# sch.net
KiCad netlist of a schematic drawn in EasyEDA
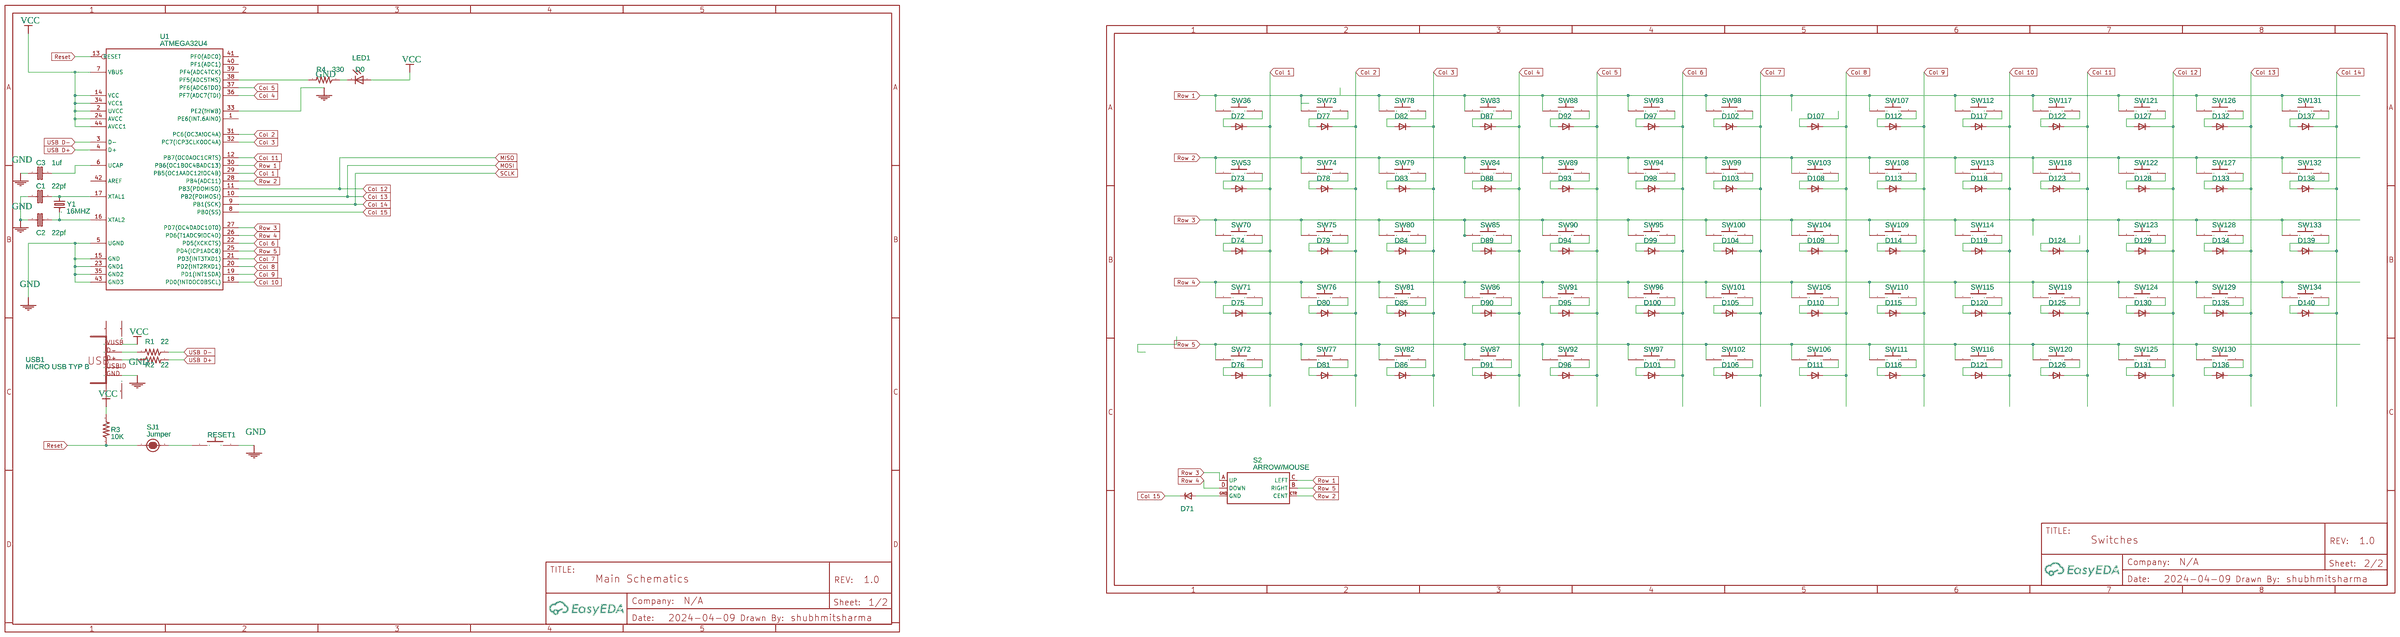
[diagram p0: Sheet_1]
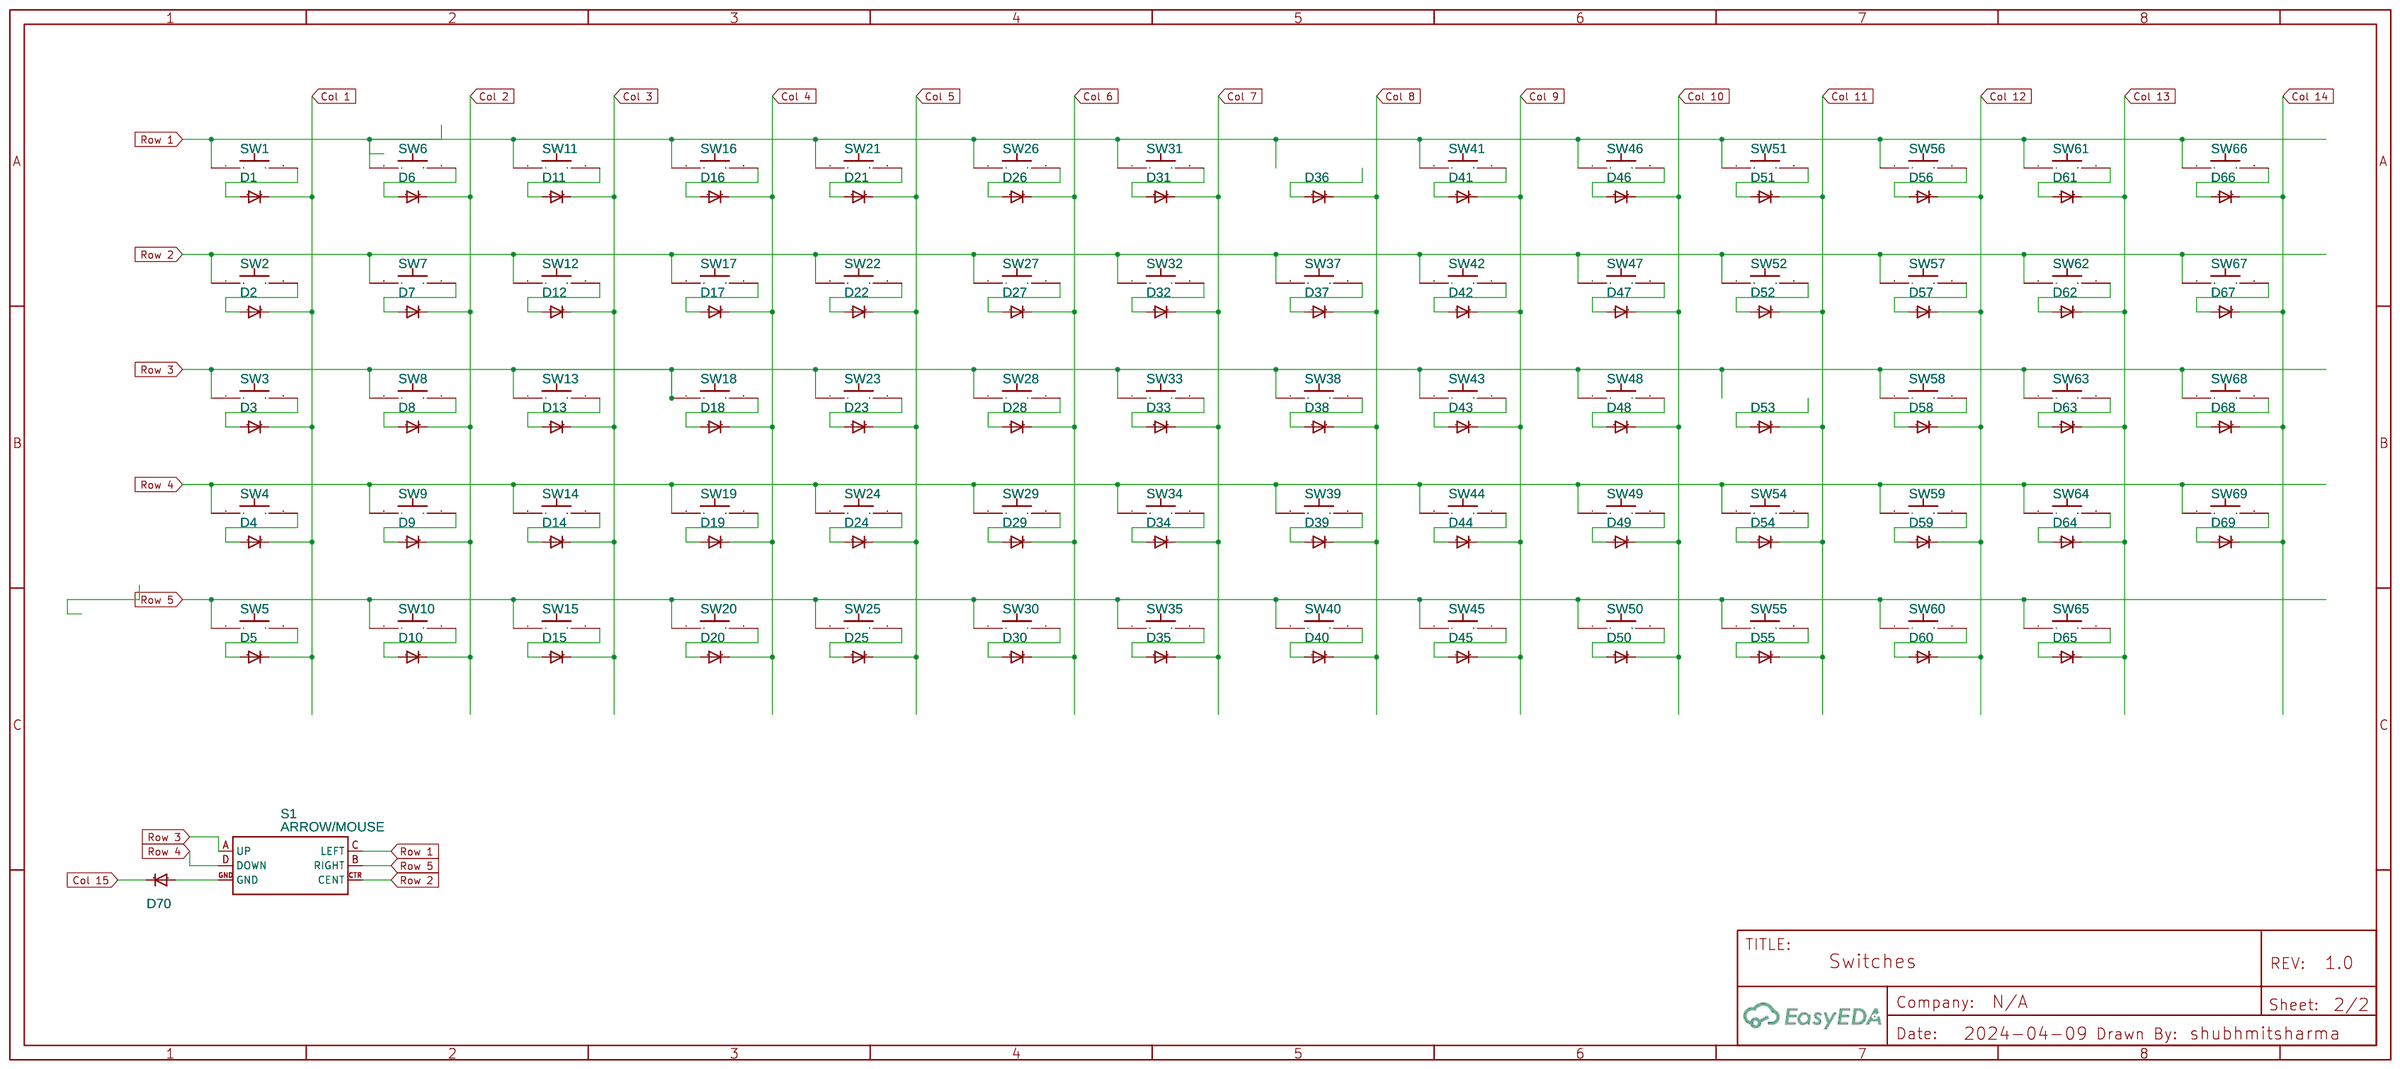
[diagram p1: Sheet_1#2]

(export (version "E")
  (design (tool "Eeschema 10.0.6"))
  (components
    (comp (ref "C1")
      (value "22pf")
      (fields (field (name "Manufacturer Part") "?"))
      (libsource (lib "") (part "Unknown_50_-560"))
    )
    (comp (ref "C2")
      (value "22pf")
      (fields (field (name "Manufacturer Part") "?"))
      (libsource (lib "") (part "Unknown_40_-530"))
    )
    (comp (ref "C3")
      (value "1uf")
      (fields (field (name "Manufacturer Part") "?"))
      (libsource (lib "") (part "Unknown_50_-590"))
    )
    (comp (ref "D71")
      (value "NO")
      (fields (field (name "Manufacturer Part") "?"))
      (libsource (lib "") (part "Unknown_1520_-175"))
    )
    (comp (ref "D72")
      (value "NO")
      (fields (field (name "Manufacturer Part") "?"))
      (libsource (lib "") (part "Unknown_1585_-650"))
    )
    (comp (ref "D73")
      (value "NO")
      (fields (field (name "Manufacturer Part") "?"))
      (libsource (lib "") (part "Unknown_1585_-570"))
    )
    (comp (ref "D74")
      (value "NO")
      (fields (field (name "Manufacturer Part") "?"))
      (libsource (lib "") (part "Unknown_1585_-490"))
    )
    (comp (ref "D75")
      (value "NO")
      (fields (field (name "Manufacturer Part") "?"))
      (libsource (lib "") (part "Unknown_1585_-410"))
    )
    (comp (ref "D76")
      (value "NO")
      (fields (field (name "Manufacturer Part") "?"))
      (libsource (lib "") (part "Unknown_1585_-330"))
    )
    (comp (ref "D77")
      (value "NO")
      (fields (field (name "Manufacturer Part") "?"))
      (libsource (lib "") (part "Unknown_1695_-650"))
    )
    (comp (ref "D78")
      (value "NO")
      (fields (field (name "Manufacturer Part") "?"))
      (libsource (lib "") (part "Unknown_1695_-570"))
    )
    (comp (ref "D79")
      (value "NO")
      (fields (field (name "Manufacturer Part") "?"))
      (libsource (lib "") (part "Unknown_1695_-490"))
    )
    (comp (ref "D80")
      (value "NO")
      (fields (field (name "Manufacturer Part") "?"))
      (libsource (lib "") (part "Unknown_1695_-410"))
    )
    (comp (ref "D81")
      (value "NO")
      (fields (field (name "Manufacturer Part") "?"))
      (libsource (lib "") (part "Unknown_1695_-330"))
    )
    (comp (ref "D82")
      (value "NO")
      (fields (field (name "Manufacturer Part") "?"))
      (libsource (lib "") (part "Unknown_1795_-650"))
    )
    (comp (ref "D83")
      (value "NO")
      (fields (field (name "Manufacturer Part") "?"))
      (libsource (lib "") (part "Unknown_1795_-570"))
    )
    (comp (ref "D84")
      (value "NO")
      (fields (field (name "Manufacturer Part") "?"))
      (libsource (lib "") (part "Unknown_1795_-490"))
    )
    (comp (ref "D85")
      (value "NO")
      (fields (field (name "Manufacturer Part") "?"))
      (libsource (lib "") (part "Unknown_1795_-410"))
    )
    (comp (ref "D86")
      (value "NO")
      (fields (field (name "Manufacturer Part") "?"))
      (libsource (lib "") (part "Unknown_1795_-330"))
    )
    (comp (ref "D87")
      (value "NO")
      (fields (field (name "Manufacturer Part") "?"))
      (libsource (lib "") (part "Unknown_1905_-650"))
    )
    (comp (ref "D88")
      (value "NO")
      (fields (field (name "Manufacturer Part") "?"))
      (libsource (lib "") (part "Unknown_1905_-570"))
    )
    (comp (ref "D89")
      (value "NO")
      (fields (field (name "Manufacturer Part") "?"))
      (libsource (lib "") (part "Unknown_1905_-490"))
    )
    (comp (ref "D90")
      (value "NO")
      (fields (field (name "Manufacturer Part") "?"))
      (libsource (lib "") (part "Unknown_1905_-410"))
    )
    (comp (ref "D91")
      (value "NO")
      (fields (field (name "Manufacturer Part") "?"))
      (libsource (lib "") (part "Unknown_1905_-330"))
    )
    (comp (ref "D92")
      (value "NO")
      (fields (field (name "Manufacturer Part") "?"))
      (libsource (lib "") (part "Unknown_2005_-650"))
    )
    (comp (ref "D93")
      (value "NO")
      (fields (field (name "Manufacturer Part") "?"))
      (libsource (lib "") (part "Unknown_2005_-570"))
    )
    (comp (ref "D94")
      (value "NO")
      (fields (field (name "Manufacturer Part") "?"))
      (libsource (lib "") (part "Unknown_2005_-490"))
    )
    (comp (ref "D95")
      (value "NO")
      (fields (field (name "Manufacturer Part") "?"))
      (libsource (lib "") (part "Unknown_2005_-410"))
    )
    (comp (ref "D96")
      (value "NO")
      (fields (field (name "Manufacturer Part") "?"))
      (libsource (lib "") (part "Unknown_2005_-330"))
    )
    (comp (ref "D97")
      (value "NO")
      (fields (field (name "Manufacturer Part") "?"))
      (libsource (lib "") (part "Unknown_2115_-650"))
    )
    (comp (ref "D98")
      (value "NO")
      (fields (field (name "Manufacturer Part") "?"))
      (libsource (lib "") (part "Unknown_2115_-570"))
    )
    (comp (ref "D99")
      (value "NO")
      (fields (field (name "Manufacturer Part") "?"))
      (libsource (lib "") (part "Unknown_2115_-490"))
    )
    (comp (ref "D100")
      (value "NO")
      (fields (field (name "Manufacturer Part") "?"))
      (libsource (lib "") (part "Unknown_2115_-410"))
    )
    (comp (ref "D101")
      (value "NO")
      (fields (field (name "Manufacturer Part") "?"))
      (libsource (lib "") (part "Unknown_2115_-330"))
    )
    (comp (ref "D102")
      (value "NO")
      (fields (field (name "Manufacturer Part") "?"))
      (libsource (lib "") (part "Unknown_2215_-650"))
    )
    (comp (ref "D103")
      (value "NO")
      (fields (field (name "Manufacturer Part") "?"))
      (libsource (lib "") (part "Unknown_2215_-570"))
    )
    (comp (ref "D104")
      (value "NO")
      (fields (field (name "Manufacturer Part") "?"))
      (libsource (lib "") (part "Unknown_2215_-490"))
    )
    (comp (ref "D105")
      (value "NO")
      (fields (field (name "Manufacturer Part") "?"))
      (libsource (lib "") (part "Unknown_2215_-410"))
    )
    (comp (ref "D106")
      (value "NO")
      (fields (field (name "Manufacturer Part") "?"))
      (libsource (lib "") (part "Unknown_2215_-330"))
    )
    (comp (ref "D107")
      (value "NO")
      (fields (field (name "Manufacturer Part") "?"))
      (libsource (lib "") (part "Unknown_2325_-650"))
    )
    (comp (ref "D108")
      (value "NO")
      (fields (field (name "Manufacturer Part") "?"))
      (libsource (lib "") (part "Unknown_2325_-570"))
    )
    (comp (ref "D109")
      (value "NO")
      (fields (field (name "Manufacturer Part") "?"))
      (libsource (lib "") (part "Unknown_2325_-490"))
    )
    (comp (ref "D110")
      (value "NO")
      (fields (field (name "Manufacturer Part") "?"))
      (libsource (lib "") (part "Unknown_2325_-410"))
    )
    (comp (ref "D111")
      (value "NO")
      (fields (field (name "Manufacturer Part") "?"))
      (libsource (lib "") (part "Unknown_2325_-330"))
    )
    (comp (ref "D112")
      (value "NO")
      (fields (field (name "Manufacturer Part") "?"))
      (libsource (lib "") (part "Unknown_2425_-650"))
    )
    (comp (ref "D113")
      (value "NO")
      (fields (field (name "Manufacturer Part") "?"))
      (libsource (lib "") (part "Unknown_2425_-570"))
    )
    (comp (ref "D114")
      (value "NO")
      (fields (field (name "Manufacturer Part") "?"))
      (libsource (lib "") (part "Unknown_2425_-490"))
    )
    (comp (ref "D115")
      (value "NO")
      (fields (field (name "Manufacturer Part") "?"))
      (libsource (lib "") (part "Unknown_2425_-410"))
    )
    (comp (ref "D116")
      (value "NO")
      (fields (field (name "Manufacturer Part") "?"))
      (libsource (lib "") (part "Unknown_2425_-330"))
    )
    (comp (ref "D117")
      (value "NO")
      (fields (field (name "Manufacturer Part") "?"))
      (libsource (lib "") (part "Unknown_2535_-650"))
    )
    (comp (ref "D118")
      (value "NO")
      (fields (field (name "Manufacturer Part") "?"))
      (libsource (lib "") (part "Unknown_2535_-570"))
    )
    (comp (ref "D119")
      (value "NO")
      (fields (field (name "Manufacturer Part") "?"))
      (libsource (lib "") (part "Unknown_2535_-490"))
    )
    (comp (ref "D120")
      (value "NO")
      (fields (field (name "Manufacturer Part") "?"))
      (libsource (lib "") (part "Unknown_2535_-410"))
    )
    (comp (ref "D121")
      (value "NO")
      (fields (field (name "Manufacturer Part") "?"))
      (libsource (lib "") (part "Unknown_2535_-330"))
    )
    (comp (ref "D122")
      (value "NO")
      (fields (field (name "Manufacturer Part") "?"))
      (libsource (lib "") (part "Unknown_2635_-650"))
    )
    (comp (ref "D123")
      (value "NO")
      (fields (field (name "Manufacturer Part") "?"))
      (libsource (lib "") (part "Unknown_2635_-570"))
    )
    (comp (ref "D124")
      (value "NO")
      (fields (field (name "Manufacturer Part") "?"))
      (libsource (lib "") (part "Unknown_2635_-490"))
    )
    (comp (ref "D125")
      (value "NO")
      (fields (field (name "Manufacturer Part") "?"))
      (libsource (lib "") (part "Unknown_2635_-410"))
    )
    (comp (ref "D126")
      (value "NO")
      (fields (field (name "Manufacturer Part") "?"))
      (libsource (lib "") (part "Unknown_2635_-330"))
    )
    (comp (ref "D127")
      (value "NO")
      (fields (field (name "Manufacturer Part") "?"))
      (libsource (lib "") (part "Unknown_2745_-650"))
    )
    (comp (ref "D128")
      (value "NO")
      (fields (field (name "Manufacturer Part") "?"))
      (libsource (lib "") (part "Unknown_2745_-570"))
    )
    (comp (ref "D129")
      (value "NO")
      (fields (field (name "Manufacturer Part") "?"))
      (libsource (lib "") (part "Unknown_2745_-490"))
    )
    (comp (ref "D130")
      (value "NO")
      (fields (field (name "Manufacturer Part") "?"))
      (libsource (lib "") (part "Unknown_2745_-410"))
    )
    (comp (ref "D131")
      (value "NO")
      (fields (field (name "Manufacturer Part") "?"))
      (libsource (lib "") (part "Unknown_2745_-330"))
    )
    (comp (ref "D132")
      (value "NO")
      (fields (field (name "Manufacturer Part") "?"))
      (libsource (lib "") (part "Unknown_2845_-650"))
    )
    (comp (ref "D133")
      (value "NO")
      (fields (field (name "Manufacturer Part") "?"))
      (libsource (lib "") (part "Unknown_2845_-570"))
    )
    (comp (ref "D134")
      (value "NO")
      (fields (field (name "Manufacturer Part") "?"))
      (libsource (lib "") (part "Unknown_2845_-490"))
    )
    (comp (ref "D135")
      (value "NO")
      (fields (field (name "Manufacturer Part") "?"))
      (libsource (lib "") (part "Unknown_2845_-410"))
    )
    (comp (ref "D136")
      (value "NO")
      (fields (field (name "Manufacturer Part") "?"))
      (libsource (lib "") (part "Unknown_2845_-330"))
    )
    (comp (ref "D137")
      (value "NO")
      (fields (field (name "Manufacturer Part") "?"))
      (libsource (lib "") (part "Unknown_2955_-650"))
    )
    (comp (ref "D138")
      (value "NO")
      (fields (field (name "Manufacturer Part") "?"))
      (libsource (lib "") (part "Unknown_2955_-570"))
    )
    (comp (ref "D139")
      (value "NO")
      (fields (field (name "Manufacturer Part") "?"))
      (libsource (lib "") (part "Unknown_2955_-490"))
    )
    (comp (ref "D140")
      (value "NO")
      (fields (field (name "Manufacturer Part") "?"))
      (libsource (lib "") (part "Unknown_2955_-410"))
    )
    (comp (ref "LED1")
      (value "D0")
      (fields (field (name "Manufacturer Part") "?"))
      (libsource (lib "") (part "Unknown_460_-710"))
    )
    (comp (ref "R1")
      (value "22")
      (fields (field (name "Manufacturer Part") "?"))
      (libsource (lib "") (part "Unknown_190_-360"))
    )
    (comp (ref "R2")
      (value "22")
      (fields (field (name "Manufacturer Part") "?"))
      (libsource (lib "") (part "Unknown_190_-350"))
    )
    (comp (ref "R3")
      (value "10K")
      (fields (field (name "Manufacturer Part") "?"))
      (libsource (lib "") (part "Unknown_130_-260"))
    )
    (comp (ref "R4")
      (value "330")
      (fields (field (name "Manufacturer Part") "?"))
      (libsource (lib "") (part "Unknown_410_-710"))
    )
    (comp (ref "RESET1")
      (value "NO")
      (fields (field (name "Manufacturer Part") "?"))
      (libsource (lib "") (part "Unknown_270_-240"))
    )
    (comp (ref "S2")
      (value "ARROW/MOUSE")
      (fields (field (name "Manufacturer Part") "?"))
      (libsource (lib "") (part "Unknown_1610_-185"))
    )
    (comp (ref "SJ1")
      (value "Jumper")
      (fields (field (name "Manufacturer Part") "?"))
      (libsource (lib "") (part "Unknown_190_-240"))
    )
    (comp (ref "SW36")
      (value "NO")
      (fields (field (name "Manufacturer Part") "?"))
      (libsource (lib "") (part "Unknown_1585_-670"))
    )
    (comp (ref "SW53")
      (value "NO")
      (fields (field (name "Manufacturer Part") "?"))
      (libsource (lib "") (part "Unknown_1585_-590"))
    )
    (comp (ref "SW70")
      (value "NO")
      (fields (field (name "Manufacturer Part") "?"))
      (libsource (lib "") (part "Unknown_1585_-510"))
    )
    (comp (ref "SW71")
      (value "NO")
      (fields (field (name "Manufacturer Part") "?"))
      (libsource (lib "") (part "Unknown_1585_-430"))
    )
    (comp (ref "SW72")
      (value "NO")
      (fields (field (name "Manufacturer Part") "?"))
      (libsource (lib "") (part "Unknown_1585_-350"))
    )
    (comp (ref "SW73")
      (value "NO")
      (fields (field (name "Manufacturer Part") "?"))
      (libsource (lib "") (part "Unknown_1695_-670"))
    )
    (comp (ref "SW74")
      (value "NO")
      (fields (field (name "Manufacturer Part") "?"))
      (libsource (lib "") (part "Unknown_1695_-590"))
    )
    (comp (ref "SW75")
      (value "NO")
      (fields (field (name "Manufacturer Part") "?"))
      (libsource (lib "") (part "Unknown_1695_-510"))
    )
    (comp (ref "SW76")
      (value "NO")
      (fields (field (name "Manufacturer Part") "?"))
      (libsource (lib "") (part "Unknown_1695_-430"))
    )
    (comp (ref "SW77")
      (value "NO")
      (fields (field (name "Manufacturer Part") "?"))
      (libsource (lib "") (part "Unknown_1695_-350"))
    )
    (comp (ref "SW78")
      (value "NO")
      (fields (field (name "Manufacturer Part") "?"))
      (libsource (lib "") (part "Unknown_1795_-670"))
    )
    (comp (ref "SW79")
      (value "NO")
      (fields (field (name "Manufacturer Part") "?"))
      (libsource (lib "") (part "Unknown_1795_-590"))
    )
    (comp (ref "SW80")
      (value "NO")
      (fields (field (name "Manufacturer Part") "?"))
      (libsource (lib "") (part "Unknown_1795_-510"))
    )
    (comp (ref "SW81")
      (value "NO")
      (fields (field (name "Manufacturer Part") "?"))
      (libsource (lib "") (part "Unknown_1795_-430"))
    )
    (comp (ref "SW82")
      (value "NO")
      (fields (field (name "Manufacturer Part") "?"))
      (libsource (lib "") (part "Unknown_1795_-350"))
    )
    (comp (ref "SW83")
      (value "NO")
      (fields (field (name "Manufacturer Part") "?"))
      (libsource (lib "") (part "Unknown_1905_-670"))
    )
    (comp (ref "SW84")
      (value "NO")
      (fields (field (name "Manufacturer Part") "?"))
      (libsource (lib "") (part "Unknown_1905_-590"))
    )
    (comp (ref "SW85")
      (value "NO")
      (fields (field (name "Manufacturer Part") "?"))
      (libsource (lib "") (part "Unknown_1905_-510"))
    )
    (comp (ref "SW86")
      (value "NO")
      (fields (field (name "Manufacturer Part") "?"))
      (libsource (lib "") (part "Unknown_1905_-430"))
    )
    (comp (ref "SW87")
      (value "NO")
      (fields (field (name "Manufacturer Part") "?"))
      (libsource (lib "") (part "Unknown_1905_-350"))
    )
    (comp (ref "SW88")
      (value "NO")
      (fields (field (name "Manufacturer Part") "?"))
      (libsource (lib "") (part "Unknown_2005_-670"))
    )
    (comp (ref "SW89")
      (value "NO")
      (fields (field (name "Manufacturer Part") "?"))
      (libsource (lib "") (part "Unknown_2005_-590"))
    )
    (comp (ref "SW90")
      (value "NO")
      (fields (field (name "Manufacturer Part") "?"))
      (libsource (lib "") (part "Unknown_2005_-510"))
    )
    (comp (ref "SW91")
      (value "NO")
      (fields (field (name "Manufacturer Part") "?"))
      (libsource (lib "") (part "Unknown_2005_-430"))
    )
    (comp (ref "SW92")
      (value "NO")
      (fields (field (name "Manufacturer Part") "?"))
      (libsource (lib "") (part "Unknown_2005_-350"))
    )
    (comp (ref "SW93")
      (value "NO")
      (fields (field (name "Manufacturer Part") "?"))
      (libsource (lib "") (part "Unknown_2115_-670"))
    )
    (comp (ref "SW94")
      (value "NO")
      (fields (field (name "Manufacturer Part") "?"))
      (libsource (lib "") (part "Unknown_2115_-590"))
    )
    (comp (ref "SW95")
      (value "NO")
      (fields (field (name "Manufacturer Part") "?"))
      (libsource (lib "") (part "Unknown_2115_-510"))
    )
    (comp (ref "SW96")
      (value "NO")
      (fields (field (name "Manufacturer Part") "?"))
      (libsource (lib "") (part "Unknown_2115_-430"))
    )
    (comp (ref "SW97")
      (value "NO")
      (fields (field (name "Manufacturer Part") "?"))
      (libsource (lib "") (part "Unknown_2115_-350"))
    )
    (comp (ref "SW98")
      (value "NO")
      (fields (field (name "Manufacturer Part") "?"))
      (libsource (lib "") (part "Unknown_2215_-670"))
    )
    (comp (ref "SW99")
      (value "NO")
      (fields (field (name "Manufacturer Part") "?"))
      (libsource (lib "") (part "Unknown_2215_-590"))
    )
    (comp (ref "SW100")
      (value "NO")
      (fields (field (name "Manufacturer Part") "?"))
      (libsource (lib "") (part "Unknown_2215_-510"))
    )
    (comp (ref "SW101")
      (value "NO")
      (fields (field (name "Manufacturer Part") "?"))
      (libsource (lib "") (part "Unknown_2215_-430"))
    )
    (comp (ref "SW102")
      (value "NO")
      (fields (field (name "Manufacturer Part") "?"))
      (libsource (lib "") (part "Unknown_2215_-350"))
    )
    (comp (ref "SW103")
      (value "NO")
      (fields (field (name "Manufacturer Part") "?"))
      (libsource (lib "") (part "Unknown_2325_-590"))
    )
    (comp (ref "SW104")
      (value "NO")
      (fields (field (name "Manufacturer Part") "?"))
      (libsource (lib "") (part "Unknown_2325_-510"))
    )
    (comp (ref "SW105")
      (value "NO")
      (fields (field (name "Manufacturer Part") "?"))
      (libsource (lib "") (part "Unknown_2325_-430"))
    )
    (comp (ref "SW106")
      (value "NO")
      (fields (field (name "Manufacturer Part") "?"))
      (libsource (lib "") (part "Unknown_2325_-350"))
    )
    (comp (ref "SW107")
      (value "NO")
      (fields (field (name "Manufacturer Part") "?"))
      (libsource (lib "") (part "Unknown_2425_-670"))
    )
    (comp (ref "SW108")
      (value "NO")
      (fields (field (name "Manufacturer Part") "?"))
      (libsource (lib "") (part "Unknown_2425_-590"))
    )
    (comp (ref "SW109")
      (value "NO")
      (fields (field (name "Manufacturer Part") "?"))
      (libsource (lib "") (part "Unknown_2425_-510"))
    )
    (comp (ref "SW110")
      (value "NO")
      (fields (field (name "Manufacturer Part") "?"))
      (libsource (lib "") (part "Unknown_2425_-430"))
    )
    (comp (ref "SW111")
      (value "NO")
      (fields (field (name "Manufacturer Part") "?"))
      (libsource (lib "") (part "Unknown_2425_-350"))
    )
    (comp (ref "SW112")
      (value "NO")
      (fields (field (name "Manufacturer Part") "?"))
      (libsource (lib "") (part "Unknown_2535_-670"))
    )
    (comp (ref "SW113")
      (value "NO")
      (fields (field (name "Manufacturer Part") "?"))
      (libsource (lib "") (part "Unknown_2535_-590"))
    )
    (comp (ref "SW114")
      (value "NO")
      (fields (field (name "Manufacturer Part") "?"))
      (libsource (lib "") (part "Unknown_2535_-510"))
    )
    (comp (ref "SW115")
      (value "NO")
      (fields (field (name "Manufacturer Part") "?"))
      (libsource (lib "") (part "Unknown_2535_-430"))
    )
    (comp (ref "SW116")
      (value "NO")
      (fields (field (name "Manufacturer Part") "?"))
      (libsource (lib "") (part "Unknown_2535_-350"))
    )
    (comp (ref "SW117")
      (value "NO")
      (fields (field (name "Manufacturer Part") "?"))
      (libsource (lib "") (part "Unknown_2635_-670"))
    )
    (comp (ref "SW118")
      (value "NO")
      (fields (field (name "Manufacturer Part") "?"))
      (libsource (lib "") (part "Unknown_2635_-590"))
    )
    (comp (ref "SW119")
      (value "NO")
      (fields (field (name "Manufacturer Part") "?"))
      (libsource (lib "") (part "Unknown_2635_-430"))
    )
    (comp (ref "SW120")
      (value "NO")
      (fields (field (name "Manufacturer Part") "?"))
      (libsource (lib "") (part "Unknown_2635_-350"))
    )
    (comp (ref "SW121")
      (value "NO")
      (fields (field (name "Manufacturer Part") "?"))
      (libsource (lib "") (part "Unknown_2745_-670"))
    )
    (comp (ref "SW122")
      (value "NO")
      (fields (field (name "Manufacturer Part") "?"))
      (libsource (lib "") (part "Unknown_2745_-590"))
    )
    (comp (ref "SW123")
      (value "NO")
      (fields (field (name "Manufacturer Part") "?"))
      (libsource (lib "") (part "Unknown_2745_-510"))
    )
    (comp (ref "SW124")
      (value "NO")
      (fields (field (name "Manufacturer Part") "?"))
      (libsource (lib "") (part "Unknown_2745_-430"))
    )
    (comp (ref "SW125")
      (value "NO")
      (fields (field (name "Manufacturer Part") "?"))
      (libsource (lib "") (part "Unknown_2745_-350"))
    )
    (comp (ref "SW126")
      (value "NO")
      (fields (field (name "Manufacturer Part") "?"))
      (libsource (lib "") (part "Unknown_2845_-670"))
    )
    (comp (ref "SW127")
      (value "NO")
      (fields (field (name "Manufacturer Part") "?"))
      (libsource (lib "") (part "Unknown_2845_-590"))
    )
    (comp (ref "SW128")
      (value "NO")
      (fields (field (name "Manufacturer Part") "?"))
      (libsource (lib "") (part "Unknown_2845_-510"))
    )
    (comp (ref "SW129")
      (value "NO")
      (fields (field (name "Manufacturer Part") "?"))
      (libsource (lib "") (part "Unknown_2845_-430"))
    )
    (comp (ref "SW130")
      (value "NO")
      (fields (field (name "Manufacturer Part") "?"))
      (libsource (lib "") (part "Unknown_2845_-350"))
    )
    (comp (ref "SW131")
      (value "NO")
      (fields (field (name "Manufacturer Part") "?"))
      (libsource (lib "") (part "Unknown_2955_-670"))
    )
    (comp (ref "SW132")
      (value "NO")
      (fields (field (name "Manufacturer Part") "?"))
      (libsource (lib "") (part "Unknown_2955_-590"))
    )
    (comp (ref "SW133")
      (value "NO")
      (fields (field (name "Manufacturer Part") "?"))
      (libsource (lib "") (part "Unknown_2955_-510"))
    )
    (comp (ref "SW134")
      (value "NO")
      (fields (field (name "Manufacturer Part") "?"))
      (libsource (lib "") (part "Unknown_2955_-430"))
    )
    (comp (ref "U1")
      (value "ATMEGA32U4")
      (fields (field (name "Manufacturer Part") "?"))
      (libsource (lib "") (part "Unknown_200_-570"))
    )
    (comp (ref "USB1")
      (value "MICRO USB TYP B")
      (fields (field (name "Manufacturer Part") "?"))
      (libsource (lib "") (part "Unknown_130_-350"))
    )
    (comp (ref "Y1")
      (value "16MHZ")
      (fields (field (name "Manufacturer Part") "?"))
      (libsource (lib "") (part "Unknown_70_-550"))
    )
    (comp (ref "D1")
      (value "NO")
      (fields (field (name "Manufacturer Part") "?"))
      (libsource (lib "") (part "Unknown_380_-535"))
    )
    (comp (ref "D2")
      (value "NO")
      (fields (field (name "Manufacturer Part") "?"))
      (libsource (lib "") (part "Unknown_380_-455"))
    )
    (comp (ref "D3")
      (value "NO")
      (fields (field (name "Manufacturer Part") "?"))
      (libsource (lib "") (part "Unknown_380_-375"))
    )
    (comp (ref "D4")
      (value "NO")
      (fields (field (name "Manufacturer Part") "?"))
      (libsource (lib "") (part "Unknown_380_-295"))
    )
    (comp (ref "D5")
      (value "NO")
      (fields (field (name "Manufacturer Part") "?"))
      (libsource (lib "") (part "Unknown_380_-215"))
    )
    (comp (ref "D6")
      (value "NO")
      (fields (field (name "Manufacturer Part") "?"))
      (libsource (lib "") (part "Unknown_490_-535"))
    )
    (comp (ref "D7")
      (value "NO")
      (fields (field (name "Manufacturer Part") "?"))
      (libsource (lib "") (part "Unknown_490_-455"))
    )
    (comp (ref "D8")
      (value "NO")
      (fields (field (name "Manufacturer Part") "?"))
      (libsource (lib "") (part "Unknown_490_-375"))
    )
    (comp (ref "D9")
      (value "NO")
      (fields (field (name "Manufacturer Part") "?"))
      (libsource (lib "") (part "Unknown_490_-295"))
    )
    (comp (ref "D10")
      (value "NO")
      (fields (field (name "Manufacturer Part") "?"))
      (libsource (lib "") (part "Unknown_490_-215"))
    )
    (comp (ref "D11")
      (value "NO")
      (fields (field (name "Manufacturer Part") "?"))
      (libsource (lib "") (part "Unknown_590_-535"))
    )
    (comp (ref "D12")
      (value "NO")
      (fields (field (name "Manufacturer Part") "?"))
      (libsource (lib "") (part "Unknown_590_-455"))
    )
    (comp (ref "D13")
      (value "NO")
      (fields (field (name "Manufacturer Part") "?"))
      (libsource (lib "") (part "Unknown_590_-375"))
    )
    (comp (ref "D14")
      (value "NO")
      (fields (field (name "Manufacturer Part") "?"))
      (libsource (lib "") (part "Unknown_590_-295"))
    )
    (comp (ref "D15")
      (value "NO")
      (fields (field (name "Manufacturer Part") "?"))
      (libsource (lib "") (part "Unknown_590_-215"))
    )
    (comp (ref "D16")
      (value "NO")
      (fields (field (name "Manufacturer Part") "?"))
      (libsource (lib "") (part "Unknown_700_-535"))
    )
    (comp (ref "D17")
      (value "NO")
      (fields (field (name "Manufacturer Part") "?"))
      (libsource (lib "") (part "Unknown_700_-455"))
    )
    (comp (ref "D18")
      (value "NO")
      (fields (field (name "Manufacturer Part") "?"))
      (libsource (lib "") (part "Unknown_700_-375"))
    )
    (comp (ref "D19")
      (value "NO")
      (fields (field (name "Manufacturer Part") "?"))
      (libsource (lib "") (part "Unknown_700_-295"))
    )
    (comp (ref "D20")
      (value "NO")
      (fields (field (name "Manufacturer Part") "?"))
      (libsource (lib "") (part "Unknown_700_-215"))
    )
    (comp (ref "D21")
      (value "NO")
      (fields (field (name "Manufacturer Part") "?"))
      (libsource (lib "") (part "Unknown_800_-535"))
    )
    (comp (ref "D22")
      (value "NO")
      (fields (field (name "Manufacturer Part") "?"))
      (libsource (lib "") (part "Unknown_800_-455"))
    )
    (comp (ref "D23")
      (value "NO")
      (fields (field (name "Manufacturer Part") "?"))
      (libsource (lib "") (part "Unknown_800_-375"))
    )
    (comp (ref "D24")
      (value "NO")
      (fields (field (name "Manufacturer Part") "?"))
      (libsource (lib "") (part "Unknown_800_-295"))
    )
    (comp (ref "D25")
      (value "NO")
      (fields (field (name "Manufacturer Part") "?"))
      (libsource (lib "") (part "Unknown_800_-215"))
    )
    (comp (ref "D26")
      (value "NO")
      (fields (field (name "Manufacturer Part") "?"))
      (libsource (lib "") (part "Unknown_910_-535"))
    )
    (comp (ref "D27")
      (value "NO")
      (fields (field (name "Manufacturer Part") "?"))
      (libsource (lib "") (part "Unknown_910_-455"))
    )
    (comp (ref "D28")
      (value "NO")
      (fields (field (name "Manufacturer Part") "?"))
      (libsource (lib "") (part "Unknown_910_-375"))
    )
    (comp (ref "D29")
      (value "NO")
      (fields (field (name "Manufacturer Part") "?"))
      (libsource (lib "") (part "Unknown_910_-295"))
    )
    (comp (ref "D30")
      (value "NO")
      (fields (field (name "Manufacturer Part") "?"))
      (libsource (lib "") (part "Unknown_910_-215"))
    )
    (comp (ref "D31")
      (value "NO")
      (fields (field (name "Manufacturer Part") "?"))
      (libsource (lib "") (part "Unknown_1010_-535"))
    )
    (comp (ref "D32")
      (value "NO")
      (fields (field (name "Manufacturer Part") "?"))
      (libsource (lib "") (part "Unknown_1010_-455"))
    )
    (comp (ref "D33")
      (value "NO")
      (fields (field (name "Manufacturer Part") "?"))
      (libsource (lib "") (part "Unknown_1010_-375"))
    )
    (comp (ref "D34")
      (value "NO")
      (fields (field (name "Manufacturer Part") "?"))
      (libsource (lib "") (part "Unknown_1010_-295"))
    )
    (comp (ref "D35")
      (value "NO")
      (fields (field (name "Manufacturer Part") "?"))
      (libsource (lib "") (part "Unknown_1010_-215"))
    )
    (comp (ref "D36")
      (value "NO")
      (fields (field (name "Manufacturer Part") "?"))
      (libsource (lib "") (part "Unknown_1120_-535"))
    )
    (comp (ref "D37")
      (value "NO")
      (fields (field (name "Manufacturer Part") "?"))
      (libsource (lib "") (part "Unknown_1120_-455"))
    )
    (comp (ref "D38")
      (value "NO")
      (fields (field (name "Manufacturer Part") "?"))
      (libsource (lib "") (part "Unknown_1120_-375"))
    )
    (comp (ref "D39")
      (value "NO")
      (fields (field (name "Manufacturer Part") "?"))
      (libsource (lib "") (part "Unknown_1120_-295"))
    )
    (comp (ref "D40")
      (value "NO")
      (fields (field (name "Manufacturer Part") "?"))
      (libsource (lib "") (part "Unknown_1120_-215"))
    )
    (comp (ref "D41")
      (value "NO")
      (fields (field (name "Manufacturer Part") "?"))
      (libsource (lib "") (part "Unknown_1220_-535"))
    )
    (comp (ref "D42")
      (value "NO")
      (fields (field (name "Manufacturer Part") "?"))
      (libsource (lib "") (part "Unknown_1220_-455"))
    )
    (comp (ref "D43")
      (value "NO")
      (fields (field (name "Manufacturer Part") "?"))
      (libsource (lib "") (part "Unknown_1220_-375"))
    )
    (comp (ref "D44")
      (value "NO")
      (fields (field (name "Manufacturer Part") "?"))
      (libsource (lib "") (part "Unknown_1220_-295"))
    )
    (comp (ref "D45")
      (value "NO")
      (fields (field (name "Manufacturer Part") "?"))
      (libsource (lib "") (part "Unknown_1220_-215"))
    )
    (comp (ref "D46")
      (value "NO")
      (fields (field (name "Manufacturer Part") "?"))
      (libsource (lib "") (part "Unknown_1330_-535"))
    )
    (comp (ref "D47")
      (value "NO")
      (fields (field (name "Manufacturer Part") "?"))
      (libsource (lib "") (part "Unknown_1330_-455"))
    )
    (comp (ref "D48")
      (value "NO")
      (fields (field (name "Manufacturer Part") "?"))
      (libsource (lib "") (part "Unknown_1330_-375"))
    )
    (comp (ref "D49")
      (value "NO")
      (fields (field (name "Manufacturer Part") "?"))
      (libsource (lib "") (part "Unknown_1330_-295"))
    )
    (comp (ref "D50")
      (value "NO")
      (fields (field (name "Manufacturer Part") "?"))
      (libsource (lib "") (part "Unknown_1330_-215"))
    )
    (comp (ref "D51")
      (value "NO")
      (fields (field (name "Manufacturer Part") "?"))
      (libsource (lib "") (part "Unknown_1430_-535"))
    )
    (comp (ref "D52")
      (value "NO")
      (fields (field (name "Manufacturer Part") "?"))
      (libsource (lib "") (part "Unknown_1430_-455"))
    )
    (comp (ref "D53")
      (value "NO")
      (fields (field (name "Manufacturer Part") "?"))
      (libsource (lib "") (part "Unknown_1430_-375"))
    )
    (comp (ref "D54")
      (value "NO")
      (fields (field (name "Manufacturer Part") "?"))
      (libsource (lib "") (part "Unknown_1430_-295"))
    )
    (comp (ref "D55")
      (value "NO")
      (fields (field (name "Manufacturer Part") "?"))
      (libsource (lib "") (part "Unknown_1430_-215"))
    )
    (comp (ref "D56")
      (value "NO")
      (fields (field (name "Manufacturer Part") "?"))
      (libsource (lib "") (part "Unknown_1540_-535"))
    )
    (comp (ref "D57")
      (value "NO")
      (fields (field (name "Manufacturer Part") "?"))
      (libsource (lib "") (part "Unknown_1540_-455"))
    )
    (comp (ref "D58")
      (value "NO")
      (fields (field (name "Manufacturer Part") "?"))
      (libsource (lib "") (part "Unknown_1540_-375"))
    )
    (comp (ref "D59")
      (value "NO")
      (fields (field (name "Manufacturer Part") "?"))
      (libsource (lib "") (part "Unknown_1540_-295"))
    )
    (comp (ref "D60")
      (value "NO")
      (fields (field (name "Manufacturer Part") "?"))
      (libsource (lib "") (part "Unknown_1540_-215"))
    )
    (comp (ref "D61")
      (value "NO")
      (fields (field (name "Manufacturer Part") "?"))
      (libsource (lib "") (part "Unknown_1640_-535"))
    )
    (comp (ref "D62")
      (value "NO")
      (fields (field (name "Manufacturer Part") "?"))
      (libsource (lib "") (part "Unknown_1640_-455"))
    )
    (comp (ref "D63")
      (value "NO")
      (fields (field (name "Manufacturer Part") "?"))
      (libsource (lib "") (part "Unknown_1640_-375"))
    )
    (comp (ref "D64")
      (value "NO")
      (fields (field (name "Manufacturer Part") "?"))
      (libsource (lib "") (part "Unknown_1640_-295"))
    )
    (comp (ref "D65")
      (value "NO")
      (fields (field (name "Manufacturer Part") "?"))
      (libsource (lib "") (part "Unknown_1640_-215"))
    )
    (comp (ref "D66")
      (value "NO")
      (fields (field (name "Manufacturer Part") "?"))
      (libsource (lib "") (part "Unknown_1750_-535"))
    )
    (comp (ref "D67")
      (value "NO")
      (fields (field (name "Manufacturer Part") "?"))
      (libsource (lib "") (part "Unknown_1750_-455"))
    )
    (comp (ref "D68")
      (value "NO")
      (fields (field (name "Manufacturer Part") "?"))
      (libsource (lib "") (part "Unknown_1750_-375"))
    )
    (comp (ref "D69")
      (value "NO")
      (fields (field (name "Manufacturer Part") "?"))
      (libsource (lib "") (part "Unknown_1750_-295"))
    )
    (comp (ref "D70")
      (value "NO")
      (fields (field (name "Manufacturer Part") "?"))
      (libsource (lib "") (part "Unknown_315_-60"))
    )
    (comp (ref "S1")
      (value "ARROW/MOUSE")
      (fields (field (name "Manufacturer Part") "?"))
      (libsource (lib "") (part "Unknown_405_-70"))
    )
    (comp (ref "SW1")
      (value "NO")
      (fields (field (name "Manufacturer Part") "?"))
      (libsource (lib "") (part "Unknown_380_-555"))
    )
    (comp (ref "SW2")
      (value "NO")
      (fields (field (name "Manufacturer Part") "?"))
      (libsource (lib "") (part "Unknown_380_-475"))
    )
    (comp (ref "SW3")
      (value "NO")
      (fields (field (name "Manufacturer Part") "?"))
      (libsource (lib "") (part "Unknown_380_-395"))
    )
    (comp (ref "SW4")
      (value "NO")
      (fields (field (name "Manufacturer Part") "?"))
      (libsource (lib "") (part "Unknown_380_-315"))
    )
    (comp (ref "SW5")
      (value "NO")
      (fields (field (name "Manufacturer Part") "?"))
      (libsource (lib "") (part "Unknown_380_-235"))
    )
    (comp (ref "SW6")
      (value "NO")
      (fields (field (name "Manufacturer Part") "?"))
      (libsource (lib "") (part "Unknown_490_-555"))
    )
    (comp (ref "SW7")
      (value "NO")
      (fields (field (name "Manufacturer Part") "?"))
      (libsource (lib "") (part "Unknown_490_-475"))
    )
    (comp (ref "SW8")
      (value "NO")
      (fields (field (name "Manufacturer Part") "?"))
      (libsource (lib "") (part "Unknown_490_-395"))
    )
    (comp (ref "SW9")
      (value "NO")
      (fields (field (name "Manufacturer Part") "?"))
      (libsource (lib "") (part "Unknown_490_-315"))
    )
    (comp (ref "SW10")
      (value "NO")
      (fields (field (name "Manufacturer Part") "?"))
      (libsource (lib "") (part "Unknown_490_-235"))
    )
    (comp (ref "SW11")
      (value "NO")
      (fields (field (name "Manufacturer Part") "?"))
      (libsource (lib "") (part "Unknown_590_-555"))
    )
    (comp (ref "SW12")
      (value "NO")
      (fields (field (name "Manufacturer Part") "?"))
      (libsource (lib "") (part "Unknown_590_-475"))
    )
    (comp (ref "SW13")
      (value "NO")
      (fields (field (name "Manufacturer Part") "?"))
      (libsource (lib "") (part "Unknown_590_-395"))
    )
    (comp (ref "SW14")
      (value "NO")
      (fields (field (name "Manufacturer Part") "?"))
      (libsource (lib "") (part "Unknown_590_-315"))
    )
    (comp (ref "SW15")
      (value "NO")
      (fields (field (name "Manufacturer Part") "?"))
      (libsource (lib "") (part "Unknown_590_-235"))
    )
    (comp (ref "SW16")
      (value "NO")
      (fields (field (name "Manufacturer Part") "?"))
      (libsource (lib "") (part "Unknown_700_-555"))
    )
    (comp (ref "SW17")
      (value "NO")
      (fields (field (name "Manufacturer Part") "?"))
      (libsource (lib "") (part "Unknown_700_-475"))
    )
    (comp (ref "SW18")
      (value "NO")
      (fields (field (name "Manufacturer Part") "?"))
      (libsource (lib "") (part "Unknown_700_-395"))
    )
    (comp (ref "SW19")
      (value "NO")
      (fields (field (name "Manufacturer Part") "?"))
      (libsource (lib "") (part "Unknown_700_-315"))
    )
    (comp (ref "SW20")
      (value "NO")
      (fields (field (name "Manufacturer Part") "?"))
      (libsource (lib "") (part "Unknown_700_-235"))
    )
    (comp (ref "SW21")
      (value "NO")
      (fields (field (name "Manufacturer Part") "?"))
      (libsource (lib "") (part "Unknown_800_-555"))
    )
    (comp (ref "SW22")
      (value "NO")
      (fields (field (name "Manufacturer Part") "?"))
      (libsource (lib "") (part "Unknown_800_-475"))
    )
    (comp (ref "SW23")
      (value "NO")
      (fields (field (name "Manufacturer Part") "?"))
      (libsource (lib "") (part "Unknown_800_-395"))
    )
    (comp (ref "SW24")
      (value "NO")
      (fields (field (name "Manufacturer Part") "?"))
      (libsource (lib "") (part "Unknown_800_-315"))
    )
    (comp (ref "SW25")
      (value "NO")
      (fields (field (name "Manufacturer Part") "?"))
      (libsource (lib "") (part "Unknown_800_-235"))
    )
    (comp (ref "SW26")
      (value "NO")
      (fields (field (name "Manufacturer Part") "?"))
      (libsource (lib "") (part "Unknown_910_-555"))
    )
    (comp (ref "SW27")
      (value "NO")
      (fields (field (name "Manufacturer Part") "?"))
      (libsource (lib "") (part "Unknown_910_-475"))
    )
    (comp (ref "SW28")
      (value "NO")
      (fields (field (name "Manufacturer Part") "?"))
      (libsource (lib "") (part "Unknown_910_-395"))
    )
    (comp (ref "SW29")
      (value "NO")
      (fields (field (name "Manufacturer Part") "?"))
      (libsource (lib "") (part "Unknown_910_-315"))
    )
    (comp (ref "SW30")
      (value "NO")
      (fields (field (name "Manufacturer Part") "?"))
      (libsource (lib "") (part "Unknown_910_-235"))
    )
    (comp (ref "SW31")
      (value "NO")
      (fields (field (name "Manufacturer Part") "?"))
      (libsource (lib "") (part "Unknown_1010_-555"))
    )
    (comp (ref "SW32")
      (value "NO")
      (fields (field (name "Manufacturer Part") "?"))
      (libsource (lib "") (part "Unknown_1010_-475"))
    )
    (comp (ref "SW33")
      (value "NO")
      (fields (field (name "Manufacturer Part") "?"))
      (libsource (lib "") (part "Unknown_1010_-395"))
    )
    (comp (ref "SW34")
      (value "NO")
      (fields (field (name "Manufacturer Part") "?"))
      (libsource (lib "") (part "Unknown_1010_-315"))
    )
    (comp (ref "SW35")
      (value "NO")
      (fields (field (name "Manufacturer Part") "?"))
      (libsource (lib "") (part "Unknown_1010_-235"))
    )
    (comp (ref "SW37")
      (value "NO")
      (fields (field (name "Manufacturer Part") "?"))
      (libsource (lib "") (part "Unknown_1120_-475"))
    )
    (comp (ref "SW38")
      (value "NO")
      (fields (field (name "Manufacturer Part") "?"))
      (libsource (lib "") (part "Unknown_1120_-395"))
    )
    (comp (ref "SW39")
      (value "NO")
      (fields (field (name "Manufacturer Part") "?"))
      (libsource (lib "") (part "Unknown_1120_-315"))
    )
    (comp (ref "SW40")
      (value "NO")
      (fields (field (name "Manufacturer Part") "?"))
      (libsource (lib "") (part "Unknown_1120_-235"))
    )
    (comp (ref "SW41")
      (value "NO")
      (fields (field (name "Manufacturer Part") "?"))
      (libsource (lib "") (part "Unknown_1220_-555"))
    )
    (comp (ref "SW42")
      (value "NO")
      (fields (field (name "Manufacturer Part") "?"))
      (libsource (lib "") (part "Unknown_1220_-475"))
    )
    (comp (ref "SW43")
      (value "NO")
      (fields (field (name "Manufacturer Part") "?"))
      (libsource (lib "") (part "Unknown_1220_-395"))
    )
    (comp (ref "SW44")
      (value "NO")
      (fields (field (name "Manufacturer Part") "?"))
      (libsource (lib "") (part "Unknown_1220_-315"))
    )
    (comp (ref "SW45")
      (value "NO")
      (fields (field (name "Manufacturer Part") "?"))
      (libsource (lib "") (part "Unknown_1220_-235"))
    )
    (comp (ref "SW46")
      (value "NO")
      (fields (field (name "Manufacturer Part") "?"))
      (libsource (lib "") (part "Unknown_1330_-555"))
    )
    (comp (ref "SW47")
      (value "NO")
      (fields (field (name "Manufacturer Part") "?"))
      (libsource (lib "") (part "Unknown_1330_-475"))
    )
    (comp (ref "SW48")
      (value "NO")
      (fields (field (name "Manufacturer Part") "?"))
      (libsource (lib "") (part "Unknown_1330_-395"))
    )
    (comp (ref "SW49")
      (value "NO")
      (fields (field (name "Manufacturer Part") "?"))
      (libsource (lib "") (part "Unknown_1330_-315"))
    )
    (comp (ref "SW50")
      (value "NO")
      (fields (field (name "Manufacturer Part") "?"))
      (libsource (lib "") (part "Unknown_1330_-235"))
    )
    (comp (ref "SW51")
      (value "NO")
      (fields (field (name "Manufacturer Part") "?"))
      (libsource (lib "") (part "Unknown_1430_-555"))
    )
    (comp (ref "SW52")
      (value "NO")
      (fields (field (name "Manufacturer Part") "?"))
      (libsource (lib "") (part "Unknown_1430_-475"))
    )
    (comp (ref "SW54")
      (value "NO")
      (fields (field (name "Manufacturer Part") "?"))
      (libsource (lib "") (part "Unknown_1430_-315"))
    )
    (comp (ref "SW55")
      (value "NO")
      (fields (field (name "Manufacturer Part") "?"))
      (libsource (lib "") (part "Unknown_1430_-235"))
    )
    (comp (ref "SW56")
      (value "NO")
      (fields (field (name "Manufacturer Part") "?"))
      (libsource (lib "") (part "Unknown_1540_-555"))
    )
    (comp (ref "SW57")
      (value "NO")
      (fields (field (name "Manufacturer Part") "?"))
      (libsource (lib "") (part "Unknown_1540_-475"))
    )
    (comp (ref "SW58")
      (value "NO")
      (fields (field (name "Manufacturer Part") "?"))
      (libsource (lib "") (part "Unknown_1540_-395"))
    )
    (comp (ref "SW59")
      (value "NO")
      (fields (field (name "Manufacturer Part") "?"))
      (libsource (lib "") (part "Unknown_1540_-315"))
    )
    (comp (ref "SW60")
      (value "NO")
      (fields (field (name "Manufacturer Part") "?"))
      (libsource (lib "") (part "Unknown_1540_-235"))
    )
    (comp (ref "SW61")
      (value "NO")
      (fields (field (name "Manufacturer Part") "?"))
      (libsource (lib "") (part "Unknown_1640_-555"))
    )
    (comp (ref "SW62")
      (value "NO")
      (fields (field (name "Manufacturer Part") "?"))
      (libsource (lib "") (part "Unknown_1640_-475"))
    )
    (comp (ref "SW63")
      (value "NO")
      (fields (field (name "Manufacturer Part") "?"))
      (libsource (lib "") (part "Unknown_1640_-395"))
    )
    (comp (ref "SW64")
      (value "NO")
      (fields (field (name "Manufacturer Part") "?"))
      (libsource (lib "") (part "Unknown_1640_-315"))
    )
    (comp (ref "SW65")
      (value "NO")
      (fields (field (name "Manufacturer Part") "?"))
      (libsource (lib "") (part "Unknown_1640_-235"))
    )
    (comp (ref "SW66")
      (value "NO")
      (fields (field (name "Manufacturer Part") "?"))
      (libsource (lib "") (part "Unknown_1750_-555"))
    )
    (comp (ref "SW67")
      (value "NO")
      (fields (field (name "Manufacturer Part") "?"))
      (libsource (lib "") (part "Unknown_1750_-475"))
    )
    (comp (ref "SW68")
      (value "NO")
      (fields (field (name "Manufacturer Part") "?"))
      (libsource (lib "") (part "Unknown_1750_-395"))
    )
    (comp (ref "SW69")
      (value "NO")
      (fields (field (name "Manufacturer Part") "?"))
      (libsource (lib "") (part "Unknown_1750_-315"))
    )
  )
  (nets
    (net (code "1") (name "Col 1") (class "Default")
      (node (ref "D1") (pin "C") (pinfunction "C_C") (pintype "unspecified"))
      (node (ref "D2") (pin "C") (pinfunction "C_C") (pintype "unspecified"))
      (node (ref "D3") (pin "C") (pinfunction "C_C") (pintype "unspecified"))
      (node (ref "D4") (pin "C") (pinfunction "C_C") (pintype "unspecified"))
      (node (ref "D5") (pin "C") (pinfunction "C_C") (pintype "unspecified"))
      (node (ref "D72") (pin "C") (pinfunction "C_C") (pintype "unspecified"))
      (node (ref "D73") (pin "C") (pinfunction "C_C") (pintype "unspecified"))
      (node (ref "D74") (pin "C") (pinfunction "C_C") (pintype "unspecified"))
      (node (ref "D75") (pin "C") (pinfunction "C_C") (pintype "unspecified"))
      (node (ref "D76") (pin "C") (pinfunction "C_C") (pintype "unspecified"))
      (node (ref "U1") (pin "29") (pinfunction "PB5(OC1AADC12!OC4B)_29") (pintype "unspecified"))
    )
    (net (code "2") (name "Col 2") (class "Default")
      (node (ref "D10") (pin "C") (pinfunction "C_C") (pintype "unspecified"))
      (node (ref "D6") (pin "C") (pinfunction "C_C") (pintype "unspecified"))
      (node (ref "D7") (pin "C") (pinfunction "C_C") (pintype "unspecified"))
      (node (ref "D77") (pin "C") (pinfunction "C_C") (pintype "unspecified"))
      (node (ref "D78") (pin "C") (pinfunction "C_C") (pintype "unspecified"))
      (node (ref "D79") (pin "C") (pinfunction "C_C") (pintype "unspecified"))
      (node (ref "D8") (pin "C") (pinfunction "C_C") (pintype "unspecified"))
      (node (ref "D80") (pin "C") (pinfunction "C_C") (pintype "unspecified"))
      (node (ref "D81") (pin "C") (pinfunction "C_C") (pintype "unspecified"))
      (node (ref "D9") (pin "C") (pinfunction "C_C") (pintype "unspecified"))
      (node (ref "U1") (pin "31") (pinfunction "PC6(OC3A!OC4A)_31") (pintype "unspecified"))
    )
    (net (code "3") (name "Col 3") (class "Default")
      (node (ref "D11") (pin "C") (pinfunction "C_C") (pintype "unspecified"))
      (node (ref "D12") (pin "C") (pinfunction "C_C") (pintype "unspecified"))
      (node (ref "D13") (pin "C") (pinfunction "C_C") (pintype "unspecified"))
      (node (ref "D14") (pin "C") (pinfunction "C_C") (pintype "unspecified"))
      (node (ref "D15") (pin "C") (pinfunction "C_C") (pintype "unspecified"))
      (node (ref "D82") (pin "C") (pinfunction "C_C") (pintype "unspecified"))
      (node (ref "D83") (pin "C") (pinfunction "C_C") (pintype "unspecified"))
      (node (ref "D84") (pin "C") (pinfunction "C_C") (pintype "unspecified"))
      (node (ref "D85") (pin "C") (pinfunction "C_C") (pintype "unspecified"))
      (node (ref "D86") (pin "C") (pinfunction "C_C") (pintype "unspecified"))
      (node (ref "U1") (pin "32") (pinfunction "PC7(ICP3CLK0OC4A)_32") (pintype "unspecified"))
    )
    (net (code "4") (name "Col 4") (class "Default")
      (node (ref "D16") (pin "C") (pinfunction "C_C") (pintype "unspecified"))
      (node (ref "D17") (pin "C") (pinfunction "C_C") (pintype "unspecified"))
      (node (ref "D18") (pin "C") (pinfunction "C_C") (pintype "unspecified"))
      (node (ref "D19") (pin "C") (pinfunction "C_C") (pintype "unspecified"))
      (node (ref "D20") (pin "C") (pinfunction "C_C") (pintype "unspecified"))
      (node (ref "D87") (pin "C") (pinfunction "C_C") (pintype "unspecified"))
      (node (ref "D88") (pin "C") (pinfunction "C_C") (pintype "unspecified"))
      (node (ref "D89") (pin "C") (pinfunction "C_C") (pintype "unspecified"))
      (node (ref "D90") (pin "C") (pinfunction "C_C") (pintype "unspecified"))
      (node (ref "D91") (pin "C") (pinfunction "C_C") (pintype "unspecified"))
      (node (ref "U1") (pin "36") (pinfunction "PF7(ADC7(TDI)_36") (pintype "unspecified"))
    )
    (net (code "5") (name "Col 5") (class "Default")
      (node (ref "D21") (pin "C") (pinfunction "C_C") (pintype "unspecified"))
      (node (ref "D22") (pin "C") (pinfunction "C_C") (pintype "unspecified"))
      (node (ref "D23") (pin "C") (pinfunction "C_C") (pintype "unspecified"))
      (node (ref "D24") (pin "C") (pinfunction "C_C") (pintype "unspecified"))
      (node (ref "D25") (pin "C") (pinfunction "C_C") (pintype "unspecified"))
      (node (ref "D92") (pin "C") (pinfunction "C_C") (pintype "unspecified"))
      (node (ref "D93") (pin "C") (pinfunction "C_C") (pintype "unspecified"))
      (node (ref "D94") (pin "C") (pinfunction "C_C") (pintype "unspecified"))
      (node (ref "D95") (pin "C") (pinfunction "C_C") (pintype "unspecified"))
      (node (ref "D96") (pin "C") (pinfunction "C_C") (pintype "unspecified"))
      (node (ref "U1") (pin "37") (pinfunction "PF6(ADC6TDO)_37") (pintype "unspecified"))
    )
    (net (code "6") (name "Col 6") (class "Default")
      (node (ref "D100") (pin "C") (pinfunction "C_C") (pintype "unspecified"))
      (node (ref "D101") (pin "C") (pinfunction "C_C") (pintype "unspecified"))
      (node (ref "D26") (pin "C") (pinfunction "C_C") (pintype "unspecified"))
      (node (ref "D27") (pin "C") (pinfunction "C_C") (pintype "unspecified"))
      (node (ref "D28") (pin "C") (pinfunction "C_C") (pintype "unspecified"))
      (node (ref "D29") (pin "C") (pinfunction "C_C") (pintype "unspecified"))
      (node (ref "D30") (pin "C") (pinfunction "C_C") (pintype "unspecified"))
      (node (ref "D97") (pin "C") (pinfunction "C_C") (pintype "unspecified"))
      (node (ref "D98") (pin "C") (pinfunction "C_C") (pintype "unspecified"))
      (node (ref "D99") (pin "C") (pinfunction "C_C") (pintype "unspecified"))
      (node (ref "U1") (pin "22") (pinfunction "PD5(XCKCTS)_22") (pintype "unspecified"))
    )
    (net (code "7") (name "Col 7") (class "Default")
      (node (ref "D102") (pin "C") (pinfunction "C_C") (pintype "unspecified"))
      (node (ref "D103") (pin "C") (pinfunction "C_C") (pintype "unspecified"))
      (node (ref "D104") (pin "C") (pinfunction "C_C") (pintype "unspecified"))
      (node (ref "D105") (pin "C") (pinfunction "C_C") (pintype "unspecified"))
      (node (ref "D106") (pin "C") (pinfunction "C_C") (pintype "unspecified"))
      (node (ref "D31") (pin "C") (pinfunction "C_C") (pintype "unspecified"))
      (node (ref "D32") (pin "C") (pinfunction "C_C") (pintype "unspecified"))
      (node (ref "D33") (pin "C") (pinfunction "C_C") (pintype "unspecified"))
      (node (ref "D34") (pin "C") (pinfunction "C_C") (pintype "unspecified"))
      (node (ref "D35") (pin "C") (pinfunction "C_C") (pintype "unspecified"))
      (node (ref "U1") (pin "21") (pinfunction "PD3(INT3TXD1)_21") (pintype "unspecified"))
    )
    (net (code "8") (name "Col 8") (class "Default")
      (node (ref "D107") (pin "C") (pinfunction "C_C") (pintype "unspecified"))
      (node (ref "D108") (pin "C") (pinfunction "C_C") (pintype "unspecified"))
      (node (ref "D109") (pin "C") (pinfunction "C_C") (pintype "unspecified"))
      (node (ref "D110") (pin "C") (pinfunction "C_C") (pintype "unspecified"))
      (node (ref "D111") (pin "C") (pinfunction "C_C") (pintype "unspecified"))
      (node (ref "D36") (pin "C") (pinfunction "C_C") (pintype "unspecified"))
      (node (ref "D37") (pin "C") (pinfunction "C_C") (pintype "unspecified"))
      (node (ref "D38") (pin "C") (pinfunction "C_C") (pintype "unspecified"))
      (node (ref "D39") (pin "C") (pinfunction "C_C") (pintype "unspecified"))
      (node (ref "D40") (pin "C") (pinfunction "C_C") (pintype "unspecified"))
      (node (ref "U1") (pin "20") (pinfunction "PD2(INT2RXD1)_20") (pintype "unspecified"))
    )
    (net (code "9") (name "Col 9") (class "Default")
      (node (ref "D112") (pin "C") (pinfunction "C_C") (pintype "unspecified"))
      (node (ref "D113") (pin "C") (pinfunction "C_C") (pintype "unspecified"))
      (node (ref "D114") (pin "C") (pinfunction "C_C") (pintype "unspecified"))
      (node (ref "D115") (pin "C") (pinfunction "C_C") (pintype "unspecified"))
      (node (ref "D116") (pin "C") (pinfunction "C_C") (pintype "unspecified"))
      (node (ref "D41") (pin "C") (pinfunction "C_C") (pintype "unspecified"))
      (node (ref "D42") (pin "C") (pinfunction "C_C") (pintype "unspecified"))
      (node (ref "D43") (pin "C") (pinfunction "C_C") (pintype "unspecified"))
      (node (ref "D44") (pin "C") (pinfunction "C_C") (pintype "unspecified"))
      (node (ref "D45") (pin "C") (pinfunction "C_C") (pintype "unspecified"))
      (node (ref "U1") (pin "19") (pinfunction "PD1(INT1SDA)_19") (pintype "unspecified"))
    )
    (net (code "10") (name "Col 10") (class "Default")
      (node (ref "D117") (pin "C") (pinfunction "C_C") (pintype "unspecified"))
      (node (ref "D118") (pin "C") (pinfunction "C_C") (pintype "unspecified"))
      (node (ref "D119") (pin "C") (pinfunction "C_C") (pintype "unspecified"))
      (node (ref "D120") (pin "C") (pinfunction "C_C") (pintype "unspecified"))
      (node (ref "D121") (pin "C") (pinfunction "C_C") (pintype "unspecified"))
      (node (ref "D46") (pin "C") (pinfunction "C_C") (pintype "unspecified"))
      (node (ref "D47") (pin "C") (pinfunction "C_C") (pintype "unspecified"))
      (node (ref "D48") (pin "C") (pinfunction "C_C") (pintype "unspecified"))
      (node (ref "D49") (pin "C") (pinfunction "C_C") (pintype "unspecified"))
      (node (ref "D50") (pin "C") (pinfunction "C_C") (pintype "unspecified"))
      (node (ref "U1") (pin "18") (pinfunction "PD0(INT0OC0BSCL)_18") (pintype "unspecified"))
    )
    (net (code "11") (name "Col 11") (class "Default")
      (node (ref "D122") (pin "C") (pinfunction "C_C") (pintype "unspecified"))
      (node (ref "D123") (pin "C") (pinfunction "C_C") (pintype "unspecified"))
      (node (ref "D124") (pin "C") (pinfunction "C_C") (pintype "unspecified"))
      (node (ref "D125") (pin "C") (pinfunction "C_C") (pintype "unspecified"))
      (node (ref "D126") (pin "C") (pinfunction "C_C") (pintype "unspecified"))
      (node (ref "D51") (pin "C") (pinfunction "C_C") (pintype "unspecified"))
      (node (ref "D52") (pin "C") (pinfunction "C_C") (pintype "unspecified"))
      (node (ref "D53") (pin "C") (pinfunction "C_C") (pintype "unspecified"))
      (node (ref "D54") (pin "C") (pinfunction "C_C") (pintype "unspecified"))
      (node (ref "D55") (pin "C") (pinfunction "C_C") (pintype "unspecified"))
      (node (ref "U1") (pin "12") (pinfunction "PB7(OC0AOC1CRTS)_12") (pintype "unspecified"))
    )
    (net (code "12") (name "Col 12") (class "Default")
      (node (ref "D127") (pin "C") (pinfunction "C_C") (pintype "unspecified"))
      (node (ref "D128") (pin "C") (pinfunction "C_C") (pintype "unspecified"))
      (node (ref "D129") (pin "C") (pinfunction "C_C") (pintype "unspecified"))
      (node (ref "D130") (pin "C") (pinfunction "C_C") (pintype "unspecified"))
      (node (ref "D131") (pin "C") (pinfunction "C_C") (pintype "unspecified"))
      (node (ref "D56") (pin "C") (pinfunction "C_C") (pintype "unspecified"))
      (node (ref "D57") (pin "C") (pinfunction "C_C") (pintype "unspecified"))
      (node (ref "D58") (pin "C") (pinfunction "C_C") (pintype "unspecified"))
      (node (ref "D59") (pin "C") (pinfunction "C_C") (pintype "unspecified"))
      (node (ref "D60") (pin "C") (pinfunction "C_C") (pintype "unspecified"))
      (node (ref "U1") (pin "11") (pinfunction "PB3(PDOMISO)_11") (pintype "unspecified"))
    )
    (net (code "13") (name "Col 13") (class "Default")
      (node (ref "D132") (pin "C") (pinfunction "C_C") (pintype "unspecified"))
      (node (ref "D133") (pin "C") (pinfunction "C_C") (pintype "unspecified"))
      (node (ref "D134") (pin "C") (pinfunction "C_C") (pintype "unspecified"))
      (node (ref "D135") (pin "C") (pinfunction "C_C") (pintype "unspecified"))
      (node (ref "D136") (pin "C") (pinfunction "C_C") (pintype "unspecified"))
      (node (ref "D61") (pin "C") (pinfunction "C_C") (pintype "unspecified"))
      (node (ref "D62") (pin "C") (pinfunction "C_C") (pintype "unspecified"))
      (node (ref "D63") (pin "C") (pinfunction "C_C") (pintype "unspecified"))
      (node (ref "D64") (pin "C") (pinfunction "C_C") (pintype "unspecified"))
      (node (ref "D65") (pin "C") (pinfunction "C_C") (pintype "unspecified"))
      (node (ref "U1") (pin "10") (pinfunction "PB2(PDIMOSI)_10") (pintype "unspecified"))
    )
    (net (code "14") (name "Col 14") (class "Default")
      (node (ref "D137") (pin "C") (pinfunction "C_C") (pintype "unspecified"))
      (node (ref "D138") (pin "C") (pinfunction "C_C") (pintype "unspecified"))
      (node (ref "D139") (pin "C") (pinfunction "C_C") (pintype "unspecified"))
      (node (ref "D140") (pin "C") (pinfunction "C_C") (pintype "unspecified"))
      (node (ref "D66") (pin "C") (pinfunction "C_C") (pintype "unspecified"))
      (node (ref "D67") (pin "C") (pinfunction "C_C") (pintype "unspecified"))
      (node (ref "D68") (pin "C") (pinfunction "C_C") (pintype "unspecified"))
      (node (ref "D69") (pin "C") (pinfunction "C_C") (pintype "unspecified"))
      (node (ref "U1") (pin "9") (pinfunction "PB1(SCK)_9") (pintype "unspecified"))
    )
    (net (code "15") (name "Col 15") (class "Default")
      (node (ref "D70") (pin "C") (pinfunction "C_C") (pintype "unspecified"))
      (node (ref "D71") (pin "C") (pinfunction "C_C") (pintype "unspecified"))
      (node (ref "U1") (pin "8") (pinfunction "PB0(SS)_8") (pintype "unspecified"))
    )
    (net (code "16") (name "GND") (class "Default")
      (node (ref "C1") (pin "1") (pinfunction "1_1") (pintype "unspecified"))
      (node (ref "C2") (pin "2") (pinfunction "2_2") (pintype "unspecified"))
      (node (ref "C3") (pin "1") (pinfunction "1_1") (pintype "unspecified"))
      (node (ref "RESET1") (pin "2") (pinfunction "2_2") (pintype "unspecified"))
      (node (ref "U1") (pin "15") (pinfunction "GND_15") (pintype "unspecified"))
      (node (ref "U1") (pin "23") (pinfunction "GND1_23") (pintype "unspecified"))
      (node (ref "U1") (pin "33") (pinfunction "PE2(!HWB)_33") (pintype "unspecified"))
      (node (ref "U1") (pin "35") (pinfunction "GND2_35") (pintype "unspecified"))
      (node (ref "U1") (pin "43") (pinfunction "GND3_43") (pintype "unspecified"))
      (node (ref "U1") (pin "5") (pinfunction "UGND_5") (pintype "unspecified"))
      (node (ref "USB1") (pin "P5") (pinfunction "GND_P5") (pintype "unspecified"))
    )
    (net (code "17") (name "Net-(D1-PadA)") (class "Default")
      (node (ref "D1") (pin "A") (pinfunction "A_A") (pintype "unspecified"))
      (node (ref "SW1") (pin "2") (pinfunction "2_2") (pintype "unspecified"))
    )
    (net (code "18") (name "Net-(D2-PadA)") (class "Default")
      (node (ref "D2") (pin "A") (pinfunction "A_A") (pintype "unspecified"))
      (node (ref "SW2") (pin "2") (pinfunction "2_2") (pintype "unspecified"))
    )
    (net (code "19") (name "Net-(D3-PadA)") (class "Default")
      (node (ref "D3") (pin "A") (pinfunction "A_A") (pintype "unspecified"))
      (node (ref "SW3") (pin "2") (pinfunction "2_2") (pintype "unspecified"))
    )
    (net (code "20") (name "Net-(D4-PadA)") (class "Default")
      (node (ref "D4") (pin "A") (pinfunction "A_A") (pintype "unspecified"))
      (node (ref "SW4") (pin "2") (pinfunction "2_2") (pintype "unspecified"))
    )
    (net (code "21") (name "Net-(D5-PadA)") (class "Default")
      (node (ref "D5") (pin "A") (pinfunction "A_A") (pintype "unspecified"))
      (node (ref "SW5") (pin "2") (pinfunction "2_2") (pintype "unspecified"))
    )
    (net (code "22") (name "Net-(D6-PadA)") (class "Default")
      (node (ref "D6") (pin "A") (pinfunction "A_A") (pintype "unspecified"))
      (node (ref "SW6") (pin "2") (pinfunction "2_2") (pintype "unspecified"))
    )
    (net (code "23") (name "Net-(D7-PadA)") (class "Default")
      (node (ref "D7") (pin "A") (pinfunction "A_A") (pintype "unspecified"))
      (node (ref "SW7") (pin "2") (pinfunction "2_2") (pintype "unspecified"))
    )
    (net (code "24") (name "Net-(D8-PadA)") (class "Default")
      (node (ref "D8") (pin "A") (pinfunction "A_A") (pintype "unspecified"))
      (node (ref "SW8") (pin "2") (pinfunction "2_2") (pintype "unspecified"))
    )
    (net (code "25") (name "Net-(D9-PadA)") (class "Default")
      (node (ref "D9") (pin "A") (pinfunction "A_A") (pintype "unspecified"))
      (node (ref "SW9") (pin "2") (pinfunction "2_2") (pintype "unspecified"))
    )
    (net (code "26") (name "Net-(D10-PadA)") (class "Default")
      (node (ref "D10") (pin "A") (pinfunction "A_A") (pintype "unspecified"))
      (node (ref "SW10") (pin "2") (pinfunction "2_2") (pintype "unspecified"))
    )
    (net (code "27") (name "Net-(D11-PadA)") (class "Default")
      (node (ref "D11") (pin "A") (pinfunction "A_A") (pintype "unspecified"))
      (node (ref "SW11") (pin "2") (pinfunction "2_2") (pintype "unspecified"))
    )
    (net (code "28") (name "Net-(D12-PadA)") (class "Default")
      (node (ref "D12") (pin "A") (pinfunction "A_A") (pintype "unspecified"))
      (node (ref "SW12") (pin "2") (pinfunction "2_2") (pintype "unspecified"))
    )
    (net (code "29") (name "Net-(D13-PadA)") (class "Default")
      (node (ref "D13") (pin "A") (pinfunction "A_A") (pintype "unspecified"))
      (node (ref "SW13") (pin "2") (pinfunction "2_2") (pintype "unspecified"))
    )
    (net (code "30") (name "Net-(D14-PadA)") (class "Default")
      (node (ref "D14") (pin "A") (pinfunction "A_A") (pintype "unspecified"))
      (node (ref "SW14") (pin "2") (pinfunction "2_2") (pintype "unspecified"))
    )
    (net (code "31") (name "Net-(D15-PadA)") (class "Default")
      (node (ref "D15") (pin "A") (pinfunction "A_A") (pintype "unspecified"))
      (node (ref "SW15") (pin "2") (pinfunction "2_2") (pintype "unspecified"))
    )
    (net (code "32") (name "Net-(D16-PadA)") (class "Default")
      (node (ref "D16") (pin "A") (pinfunction "A_A") (pintype "unspecified"))
      (node (ref "SW16") (pin "2") (pinfunction "2_2") (pintype "unspecified"))
    )
    (net (code "33") (name "Net-(D17-PadA)") (class "Default")
      (node (ref "D17") (pin "A") (pinfunction "A_A") (pintype "unspecified"))
      (node (ref "SW17") (pin "2") (pinfunction "2_2") (pintype "unspecified"))
    )
    (net (code "34") (name "Net-(D18-PadA)") (class "Default")
      (node (ref "D18") (pin "A") (pinfunction "A_A") (pintype "unspecified"))
      (node (ref "SW18") (pin "2") (pinfunction "2_2") (pintype "unspecified"))
    )
    (net (code "35") (name "Net-(D19-PadA)") (class "Default")
      (node (ref "D19") (pin "A") (pinfunction "A_A") (pintype "unspecified"))
      (node (ref "SW19") (pin "2") (pinfunction "2_2") (pintype "unspecified"))
    )
    (net (code "36") (name "Net-(D20-PadA)") (class "Default")
      (node (ref "D20") (pin "A") (pinfunction "A_A") (pintype "unspecified"))
      (node (ref "SW20") (pin "2") (pinfunction "2_2") (pintype "unspecified"))
    )
    (net (code "37") (name "Net-(D21-PadA)") (class "Default")
      (node (ref "D21") (pin "A") (pinfunction "A_A") (pintype "unspecified"))
      (node (ref "SW21") (pin "2") (pinfunction "2_2") (pintype "unspecified"))
    )
    (net (code "38") (name "Net-(D22-PadA)") (class "Default")
      (node (ref "D22") (pin "A") (pinfunction "A_A") (pintype "unspecified"))
      (node (ref "SW22") (pin "2") (pinfunction "2_2") (pintype "unspecified"))
    )
    (net (code "39") (name "Net-(D23-PadA)") (class "Default")
      (node (ref "D23") (pin "A") (pinfunction "A_A") (pintype "unspecified"))
      (node (ref "SW23") (pin "2") (pinfunction "2_2") (pintype "unspecified"))
    )
    (net (code "40") (name "Net-(D24-PadA)") (class "Default")
      (node (ref "D24") (pin "A") (pinfunction "A_A") (pintype "unspecified"))
      (node (ref "SW24") (pin "2") (pinfunction "2_2") (pintype "unspecified"))
    )
    (net (code "41") (name "Net-(D25-PadA)") (class "Default")
      (node (ref "D25") (pin "A") (pinfunction "A_A") (pintype "unspecified"))
      (node (ref "SW25") (pin "2") (pinfunction "2_2") (pintype "unspecified"))
    )
    (net (code "42") (name "Net-(D26-PadA)") (class "Default")
      (node (ref "D26") (pin "A") (pinfunction "A_A") (pintype "unspecified"))
      (node (ref "SW26") (pin "2") (pinfunction "2_2") (pintype "unspecified"))
    )
    (net (code "43") (name "Net-(D27-PadA)") (class "Default")
      (node (ref "D27") (pin "A") (pinfunction "A_A") (pintype "unspecified"))
      (node (ref "SW27") (pin "2") (pinfunction "2_2") (pintype "unspecified"))
    )
    (net (code "44") (name "Net-(D28-PadA)") (class "Default")
      (node (ref "D28") (pin "A") (pinfunction "A_A") (pintype "unspecified"))
      (node (ref "SW28") (pin "2") (pinfunction "2_2") (pintype "unspecified"))
    )
    (net (code "45") (name "Net-(D29-PadA)") (class "Default")
      (node (ref "D29") (pin "A") (pinfunction "A_A") (pintype "unspecified"))
      (node (ref "SW29") (pin "2") (pinfunction "2_2") (pintype "unspecified"))
    )
    (net (code "46") (name "Net-(D30-PadA)") (class "Default")
      (node (ref "D30") (pin "A") (pinfunction "A_A") (pintype "unspecified"))
      (node (ref "SW30") (pin "2") (pinfunction "2_2") (pintype "unspecified"))
    )
    (net (code "47") (name "Net-(D31-PadA)") (class "Default")
      (node (ref "D31") (pin "A") (pinfunction "A_A") (pintype "unspecified"))
      (node (ref "SW31") (pin "2") (pinfunction "2_2") (pintype "unspecified"))
    )
    (net (code "48") (name "Net-(D32-PadA)") (class "Default")
      (node (ref "D32") (pin "A") (pinfunction "A_A") (pintype "unspecified"))
      (node (ref "SW32") (pin "2") (pinfunction "2_2") (pintype "unspecified"))
    )
    (net (code "49") (name "Net-(D33-PadA)") (class "Default")
      (node (ref "D33") (pin "A") (pinfunction "A_A") (pintype "unspecified"))
      (node (ref "SW33") (pin "2") (pinfunction "2_2") (pintype "unspecified"))
    )
    (net (code "50") (name "Net-(D34-PadA)") (class "Default")
      (node (ref "D34") (pin "A") (pinfunction "A_A") (pintype "unspecified"))
      (node (ref "SW34") (pin "2") (pinfunction "2_2") (pintype "unspecified"))
    )
    (net (code "51") (name "Net-(D35-PadA)") (class "Default")
      (node (ref "D35") (pin "A") (pinfunction "A_A") (pintype "unspecified"))
      (node (ref "SW35") (pin "2") (pinfunction "2_2") (pintype "unspecified"))
    )
    (net (code "52") (name "Net-(D37-PadA)") (class "Default")
      (node (ref "D37") (pin "A") (pinfunction "A_A") (pintype "unspecified"))
      (node (ref "SW37") (pin "2") (pinfunction "2_2") (pintype "unspecified"))
    )
    (net (code "53") (name "Net-(D38-PadA)") (class "Default")
      (node (ref "D38") (pin "A") (pinfunction "A_A") (pintype "unspecified"))
      (node (ref "SW38") (pin "2") (pinfunction "2_2") (pintype "unspecified"))
    )
    (net (code "54") (name "Net-(D39-PadA)") (class "Default")
      (node (ref "D39") (pin "A") (pinfunction "A_A") (pintype "unspecified"))
      (node (ref "SW39") (pin "2") (pinfunction "2_2") (pintype "unspecified"))
    )
    (net (code "55") (name "Net-(D40-PadA)") (class "Default")
      (node (ref "D40") (pin "A") (pinfunction "A_A") (pintype "unspecified"))
      (node (ref "SW40") (pin "2") (pinfunction "2_2") (pintype "unspecified"))
    )
    (net (code "56") (name "Net-(D41-PadA)") (class "Default")
      (node (ref "D41") (pin "A") (pinfunction "A_A") (pintype "unspecified"))
      (node (ref "SW41") (pin "2") (pinfunction "2_2") (pintype "unspecified"))
    )
    (net (code "57") (name "Net-(D42-PadA)") (class "Default")
      (node (ref "D42") (pin "A") (pinfunction "A_A") (pintype "unspecified"))
      (node (ref "SW42") (pin "2") (pinfunction "2_2") (pintype "unspecified"))
    )
    (net (code "58") (name "Net-(D43-PadA)") (class "Default")
      (node (ref "D43") (pin "A") (pinfunction "A_A") (pintype "unspecified"))
      (node (ref "SW43") (pin "2") (pinfunction "2_2") (pintype "unspecified"))
    )
    (net (code "59") (name "Net-(D44-PadA)") (class "Default")
      (node (ref "D44") (pin "A") (pinfunction "A_A") (pintype "unspecified"))
      (node (ref "SW44") (pin "2") (pinfunction "2_2") (pintype "unspecified"))
    )
    (net (code "60") (name "Net-(D45-PadA)") (class "Default")
      (node (ref "D45") (pin "A") (pinfunction "A_A") (pintype "unspecified"))
      (node (ref "SW45") (pin "2") (pinfunction "2_2") (pintype "unspecified"))
    )
    (net (code "61") (name "Net-(D46-PadA)") (class "Default")
      (node (ref "D46") (pin "A") (pinfunction "A_A") (pintype "unspecified"))
      (node (ref "SW46") (pin "2") (pinfunction "2_2") (pintype "unspecified"))
    )
    (net (code "62") (name "Net-(D47-PadA)") (class "Default")
      (node (ref "D47") (pin "A") (pinfunction "A_A") (pintype "unspecified"))
      (node (ref "SW47") (pin "2") (pinfunction "2_2") (pintype "unspecified"))
    )
    (net (code "63") (name "Net-(D48-PadA)") (class "Default")
      (node (ref "D48") (pin "A") (pinfunction "A_A") (pintype "unspecified"))
      (node (ref "SW48") (pin "2") (pinfunction "2_2") (pintype "unspecified"))
    )
    (net (code "64") (name "Net-(D49-PadA)") (class "Default")
      (node (ref "D49") (pin "A") (pinfunction "A_A") (pintype "unspecified"))
      (node (ref "SW49") (pin "2") (pinfunction "2_2") (pintype "unspecified"))
    )
    (net (code "65") (name "Net-(D50-PadA)") (class "Default")
      (node (ref "D50") (pin "A") (pinfunction "A_A") (pintype "unspecified"))
      (node (ref "SW50") (pin "2") (pinfunction "2_2") (pintype "unspecified"))
    )
    (net (code "66") (name "Net-(D51-PadA)") (class "Default")
      (node (ref "D51") (pin "A") (pinfunction "A_A") (pintype "unspecified"))
      (node (ref "SW51") (pin "2") (pinfunction "2_2") (pintype "unspecified"))
    )
    (net (code "67") (name "Net-(D52-PadA)") (class "Default")
      (node (ref "D52") (pin "A") (pinfunction "A_A") (pintype "unspecified"))
      (node (ref "SW52") (pin "2") (pinfunction "2_2") (pintype "unspecified"))
    )
    (net (code "68") (name "Net-(D54-PadA)") (class "Default")
      (node (ref "D54") (pin "A") (pinfunction "A_A") (pintype "unspecified"))
      (node (ref "SW54") (pin "2") (pinfunction "2_2") (pintype "unspecified"))
    )
    (net (code "69") (name "Net-(D55-PadA)") (class "Default")
      (node (ref "D55") (pin "A") (pinfunction "A_A") (pintype "unspecified"))
      (node (ref "SW55") (pin "2") (pinfunction "2_2") (pintype "unspecified"))
    )
    (net (code "70") (name "Net-(D56-PadA)") (class "Default")
      (node (ref "D56") (pin "A") (pinfunction "A_A") (pintype "unspecified"))
      (node (ref "SW56") (pin "2") (pinfunction "2_2") (pintype "unspecified"))
    )
    (net (code "71") (name "Net-(D57-PadA)") (class "Default")
      (node (ref "D57") (pin "A") (pinfunction "A_A") (pintype "unspecified"))
      (node (ref "SW57") (pin "2") (pinfunction "2_2") (pintype "unspecified"))
    )
    (net (code "72") (name "Net-(D58-PadA)") (class "Default")
      (node (ref "D58") (pin "A") (pinfunction "A_A") (pintype "unspecified"))
      (node (ref "SW58") (pin "2") (pinfunction "2_2") (pintype "unspecified"))
    )
    (net (code "73") (name "Net-(D59-PadA)") (class "Default")
      (node (ref "D59") (pin "A") (pinfunction "A_A") (pintype "unspecified"))
      (node (ref "SW59") (pin "2") (pinfunction "2_2") (pintype "unspecified"))
    )
    (net (code "74") (name "Net-(D60-PadA)") (class "Default")
      (node (ref "D60") (pin "A") (pinfunction "A_A") (pintype "unspecified"))
      (node (ref "SW60") (pin "2") (pinfunction "2_2") (pintype "unspecified"))
    )
    (net (code "75") (name "Net-(D61-PadA)") (class "Default")
      (node (ref "D61") (pin "A") (pinfunction "A_A") (pintype "unspecified"))
      (node (ref "SW61") (pin "2") (pinfunction "2_2") (pintype "unspecified"))
    )
    (net (code "76") (name "Net-(D62-PadA)") (class "Default")
      (node (ref "D62") (pin "A") (pinfunction "A_A") (pintype "unspecified"))
      (node (ref "SW62") (pin "2") (pinfunction "2_2") (pintype "unspecified"))
    )
    (net (code "77") (name "Net-(D63-PadA)") (class "Default")
      (node (ref "D63") (pin "A") (pinfunction "A_A") (pintype "unspecified"))
      (node (ref "SW63") (pin "2") (pinfunction "2_2") (pintype "unspecified"))
    )
    (net (code "78") (name "Net-(D64-PadA)") (class "Default")
      (node (ref "D64") (pin "A") (pinfunction "A_A") (pintype "unspecified"))
      (node (ref "SW64") (pin "2") (pinfunction "2_2") (pintype "unspecified"))
    )
    (net (code "79") (name "Net-(D65-PadA)") (class "Default")
      (node (ref "D65") (pin "A") (pinfunction "A_A") (pintype "unspecified"))
      (node (ref "SW65") (pin "2") (pinfunction "2_2") (pintype "unspecified"))
    )
    (net (code "80") (name "Net-(D66-PadA)") (class "Default")
      (node (ref "D66") (pin "A") (pinfunction "A_A") (pintype "unspecified"))
      (node (ref "SW66") (pin "2") (pinfunction "2_2") (pintype "unspecified"))
    )
    (net (code "81") (name "Net-(D67-PadA)") (class "Default")
      (node (ref "D67") (pin "A") (pinfunction "A_A") (pintype "unspecified"))
      (node (ref "SW67") (pin "2") (pinfunction "2_2") (pintype "unspecified"))
    )
    (net (code "82") (name "Net-(D68-PadA)") (class "Default")
      (node (ref "D68") (pin "A") (pinfunction "A_A") (pintype "unspecified"))
      (node (ref "SW68") (pin "2") (pinfunction "2_2") (pintype "unspecified"))
    )
    (net (code "83") (name "Net-(D69-PadA)") (class "Default")
      (node (ref "D69") (pin "A") (pinfunction "A_A") (pintype "unspecified"))
      (node (ref "SW69") (pin "2") (pinfunction "2_2") (pintype "unspecified"))
    )
    (net (code "84") (name "Net-(D70-PadA)") (class "Default")
      (node (ref "D70") (pin "A") (pinfunction "A_A") (pintype "unspecified"))
      (node (ref "S1") (pin "GND") (pinfunction "GND_GND") (pintype "unspecified"))
    )
    (net (code "85") (name "Net-(D71-PadA)") (class "Default")
      (node (ref "D71") (pin "A") (pinfunction "A_A") (pintype "unspecified"))
      (node (ref "S2") (pin "GND") (pinfunction "GND_GND") (pintype "unspecified"))
    )
    (net (code "86") (name "Net-(D72-PadA)") (class "Default")
      (node (ref "D72") (pin "A") (pinfunction "A_A") (pintype "unspecified"))
      (node (ref "SW36") (pin "2") (pinfunction "2_2") (pintype "unspecified"))
    )
    (net (code "87") (name "Net-(D73-PadA)") (class "Default")
      (node (ref "D73") (pin "A") (pinfunction "A_A") (pintype "unspecified"))
      (node (ref "SW53") (pin "2") (pinfunction "2_2") (pintype "unspecified"))
    )
    (net (code "88") (name "Net-(D74-PadA)") (class "Default")
      (node (ref "D74") (pin "A") (pinfunction "A_A") (pintype "unspecified"))
      (node (ref "SW70") (pin "2") (pinfunction "2_2") (pintype "unspecified"))
    )
    (net (code "89") (name "Net-(D75-PadA)") (class "Default")
      (node (ref "D75") (pin "A") (pinfunction "A_A") (pintype "unspecified"))
      (node (ref "SW71") (pin "2") (pinfunction "2_2") (pintype "unspecified"))
    )
    (net (code "90") (name "Net-(D76-PadA)") (class "Default")
      (node (ref "D76") (pin "A") (pinfunction "A_A") (pintype "unspecified"))
      (node (ref "SW72") (pin "2") (pinfunction "2_2") (pintype "unspecified"))
    )
    (net (code "91") (name "Net-(D77-PadA)") (class "Default")
      (node (ref "D77") (pin "A") (pinfunction "A_A") (pintype "unspecified"))
      (node (ref "SW73") (pin "2") (pinfunction "2_2") (pintype "unspecified"))
    )
    (net (code "92") (name "Net-(D78-PadA)") (class "Default")
      (node (ref "D78") (pin "A") (pinfunction "A_A") (pintype "unspecified"))
      (node (ref "SW74") (pin "2") (pinfunction "2_2") (pintype "unspecified"))
    )
    (net (code "93") (name "Net-(D79-PadA)") (class "Default")
      (node (ref "D79") (pin "A") (pinfunction "A_A") (pintype "unspecified"))
      (node (ref "SW75") (pin "2") (pinfunction "2_2") (pintype "unspecified"))
    )
    (net (code "94") (name "Net-(D80-PadA)") (class "Default")
      (node (ref "D80") (pin "A") (pinfunction "A_A") (pintype "unspecified"))
      (node (ref "SW76") (pin "2") (pinfunction "2_2") (pintype "unspecified"))
    )
    (net (code "95") (name "Net-(D81-PadA)") (class "Default")
      (node (ref "D81") (pin "A") (pinfunction "A_A") (pintype "unspecified"))
      (node (ref "SW77") (pin "2") (pinfunction "2_2") (pintype "unspecified"))
    )
    (net (code "96") (name "Net-(D82-PadA)") (class "Default")
      (node (ref "D82") (pin "A") (pinfunction "A_A") (pintype "unspecified"))
      (node (ref "SW78") (pin "2") (pinfunction "2_2") (pintype "unspecified"))
    )
    (net (code "97") (name "Net-(D83-PadA)") (class "Default")
      (node (ref "D83") (pin "A") (pinfunction "A_A") (pintype "unspecified"))
      (node (ref "SW79") (pin "2") (pinfunction "2_2") (pintype "unspecified"))
    )
    (net (code "98") (name "Net-(D84-PadA)") (class "Default")
      (node (ref "D84") (pin "A") (pinfunction "A_A") (pintype "unspecified"))
      (node (ref "SW80") (pin "2") (pinfunction "2_2") (pintype "unspecified"))
    )
    (net (code "99") (name "Net-(D85-PadA)") (class "Default")
      (node (ref "D85") (pin "A") (pinfunction "A_A") (pintype "unspecified"))
      (node (ref "SW81") (pin "2") (pinfunction "2_2") (pintype "unspecified"))
    )
    (net (code "100") (name "Net-(D86-PadA)") (class "Default")
      (node (ref "D86") (pin "A") (pinfunction "A_A") (pintype "unspecified"))
      (node (ref "SW82") (pin "2") (pinfunction "2_2") (pintype "unspecified"))
    )
    (net (code "101") (name "Net-(D87-PadA)") (class "Default")
      (node (ref "D87") (pin "A") (pinfunction "A_A") (pintype "unspecified"))
      (node (ref "SW83") (pin "2") (pinfunction "2_2") (pintype "unspecified"))
    )
    (net (code "102") (name "Net-(D88-PadA)") (class "Default")
      (node (ref "D88") (pin "A") (pinfunction "A_A") (pintype "unspecified"))
      (node (ref "SW84") (pin "2") (pinfunction "2_2") (pintype "unspecified"))
    )
    (net (code "103") (name "Net-(D89-PadA)") (class "Default")
      (node (ref "D89") (pin "A") (pinfunction "A_A") (pintype "unspecified"))
      (node (ref "SW85") (pin "2") (pinfunction "2_2") (pintype "unspecified"))
    )
    (net (code "104") (name "Net-(D90-PadA)") (class "Default")
      (node (ref "D90") (pin "A") (pinfunction "A_A") (pintype "unspecified"))
      (node (ref "SW86") (pin "2") (pinfunction "2_2") (pintype "unspecified"))
    )
    (net (code "105") (name "Net-(D91-PadA)") (class "Default")
      (node (ref "D91") (pin "A") (pinfunction "A_A") (pintype "unspecified"))
      (node (ref "SW87") (pin "2") (pinfunction "2_2") (pintype "unspecified"))
    )
    (net (code "106") (name "Net-(D92-PadA)") (class "Default")
      (node (ref "D92") (pin "A") (pinfunction "A_A") (pintype "unspecified"))
      (node (ref "SW88") (pin "2") (pinfunction "2_2") (pintype "unspecified"))
    )
    (net (code "107") (name "Net-(D93-PadA)") (class "Default")
      (node (ref "D93") (pin "A") (pinfunction "A_A") (pintype "unspecified"))
      (node (ref "SW89") (pin "2") (pinfunction "2_2") (pintype "unspecified"))
    )
    (net (code "108") (name "Net-(D94-PadA)") (class "Default")
      (node (ref "D94") (pin "A") (pinfunction "A_A") (pintype "unspecified"))
      (node (ref "SW90") (pin "2") (pinfunction "2_2") (pintype "unspecified"))
    )
    (net (code "109") (name "Net-(D95-PadA)") (class "Default")
      (node (ref "D95") (pin "A") (pinfunction "A_A") (pintype "unspecified"))
      (node (ref "SW91") (pin "2") (pinfunction "2_2") (pintype "unspecified"))
    )
    (net (code "110") (name "Net-(D96-PadA)") (class "Default")
      (node (ref "D96") (pin "A") (pinfunction "A_A") (pintype "unspecified"))
      (node (ref "SW92") (pin "2") (pinfunction "2_2") (pintype "unspecified"))
    )
    (net (code "111") (name "Net-(D97-PadA)") (class "Default")
      (node (ref "D97") (pin "A") (pinfunction "A_A") (pintype "unspecified"))
      (node (ref "SW93") (pin "2") (pinfunction "2_2") (pintype "unspecified"))
    )
    (net (code "112") (name "Net-(D98-PadA)") (class "Default")
      (node (ref "D98") (pin "A") (pinfunction "A_A") (pintype "unspecified"))
      (node (ref "SW94") (pin "2") (pinfunction "2_2") (pintype "unspecified"))
    )
    (net (code "113") (name "Net-(D99-PadA)") (class "Default")
      (node (ref "D99") (pin "A") (pinfunction "A_A") (pintype "unspecified"))
      (node (ref "SW95") (pin "2") (pinfunction "2_2") (pintype "unspecified"))
    )
    (net (code "114") (name "Net-(D100-PadA)") (class "Default")
      (node (ref "D100") (pin "A") (pinfunction "A_A") (pintype "unspecified"))
      (node (ref "SW96") (pin "2") (pinfunction "2_2") (pintype "unspecified"))
    )
    (net (code "115") (name "Net-(D101-PadA)") (class "Default")
      (node (ref "D101") (pin "A") (pinfunction "A_A") (pintype "unspecified"))
      (node (ref "SW97") (pin "2") (pinfunction "2_2") (pintype "unspecified"))
    )
    (net (code "116") (name "Net-(D102-PadA)") (class "Default")
      (node (ref "D102") (pin "A") (pinfunction "A_A") (pintype "unspecified"))
      (node (ref "SW98") (pin "2") (pinfunction "2_2") (pintype "unspecified"))
    )
    (net (code "117") (name "Net-(D103-PadA)") (class "Default")
      (node (ref "D103") (pin "A") (pinfunction "A_A") (pintype "unspecified"))
      (node (ref "SW99") (pin "2") (pinfunction "2_2") (pintype "unspecified"))
    )
    (net (code "118") (name "Net-(D104-PadA)") (class "Default")
      (node (ref "D104") (pin "A") (pinfunction "A_A") (pintype "unspecified"))
      (node (ref "SW100") (pin "2") (pinfunction "2_2") (pintype "unspecified"))
    )
    (net (code "119") (name "Net-(D105-PadA)") (class "Default")
      (node (ref "D105") (pin "A") (pinfunction "A_A") (pintype "unspecified"))
      (node (ref "SW101") (pin "2") (pinfunction "2_2") (pintype "unspecified"))
    )
    (net (code "120") (name "Net-(D106-PadA)") (class "Default")
      (node (ref "D106") (pin "A") (pinfunction "A_A") (pintype "unspecified"))
      (node (ref "SW102") (pin "2") (pinfunction "2_2") (pintype "unspecified"))
    )
    (net (code "121") (name "Net-(D108-PadA)") (class "Default")
      (node (ref "D108") (pin "A") (pinfunction "A_A") (pintype "unspecified"))
      (node (ref "SW103") (pin "2") (pinfunction "2_2") (pintype "unspecified"))
    )
    (net (code "122") (name "Net-(D109-PadA)") (class "Default")
      (node (ref "D109") (pin "A") (pinfunction "A_A") (pintype "unspecified"))
      (node (ref "SW104") (pin "2") (pinfunction "2_2") (pintype "unspecified"))
    )
    (net (code "123") (name "Net-(D110-PadA)") (class "Default")
      (node (ref "D110") (pin "A") (pinfunction "A_A") (pintype "unspecified"))
      (node (ref "SW105") (pin "2") (pinfunction "2_2") (pintype "unspecified"))
    )
    (net (code "124") (name "Net-(D111-PadA)") (class "Default")
      (node (ref "D111") (pin "A") (pinfunction "A_A") (pintype "unspecified"))
      (node (ref "SW106") (pin "2") (pinfunction "2_2") (pintype "unspecified"))
    )
    (net (code "125") (name "Net-(D112-PadA)") (class "Default")
      (node (ref "D112") (pin "A") (pinfunction "A_A") (pintype "unspecified"))
      (node (ref "SW107") (pin "2") (pinfunction "2_2") (pintype "unspecified"))
    )
    (net (code "126") (name "Net-(D113-PadA)") (class "Default")
      (node (ref "D113") (pin "A") (pinfunction "A_A") (pintype "unspecified"))
      (node (ref "SW108") (pin "2") (pinfunction "2_2") (pintype "unspecified"))
    )
    (net (code "127") (name "Net-(D114-PadA)") (class "Default")
      (node (ref "D114") (pin "A") (pinfunction "A_A") (pintype "unspecified"))
      (node (ref "SW109") (pin "2") (pinfunction "2_2") (pintype "unspecified"))
    )
    (net (code "128") (name "Net-(D115-PadA)") (class "Default")
      (node (ref "D115") (pin "A") (pinfunction "A_A") (pintype "unspecified"))
      (node (ref "SW110") (pin "2") (pinfunction "2_2") (pintype "unspecified"))
    )
    (net (code "129") (name "Net-(D116-PadA)") (class "Default")
      (node (ref "D116") (pin "A") (pinfunction "A_A") (pintype "unspecified"))
      (node (ref "SW111") (pin "2") (pinfunction "2_2") (pintype "unspecified"))
    )
    (net (code "130") (name "Net-(D117-PadA)") (class "Default")
      (node (ref "D117") (pin "A") (pinfunction "A_A") (pintype "unspecified"))
      (node (ref "SW112") (pin "2") (pinfunction "2_2") (pintype "unspecified"))
    )
    (net (code "131") (name "Net-(D118-PadA)") (class "Default")
      (node (ref "D118") (pin "A") (pinfunction "A_A") (pintype "unspecified"))
      (node (ref "SW113") (pin "2") (pinfunction "2_2") (pintype "unspecified"))
    )
    (net (code "132") (name "Net-(D119-PadA)") (class "Default")
      (node (ref "D119") (pin "A") (pinfunction "A_A") (pintype "unspecified"))
      (node (ref "SW114") (pin "2") (pinfunction "2_2") (pintype "unspecified"))
    )
    (net (code "133") (name "Net-(D120-PadA)") (class "Default")
      (node (ref "D120") (pin "A") (pinfunction "A_A") (pintype "unspecified"))
      (node (ref "SW115") (pin "2") (pinfunction "2_2") (pintype "unspecified"))
    )
    (net (code "134") (name "Net-(D121-PadA)") (class "Default")
      (node (ref "D121") (pin "A") (pinfunction "A_A") (pintype "unspecified"))
      (node (ref "SW116") (pin "2") (pinfunction "2_2") (pintype "unspecified"))
    )
    (net (code "135") (name "Net-(D122-PadA)") (class "Default")
      (node (ref "D122") (pin "A") (pinfunction "A_A") (pintype "unspecified"))
      (node (ref "SW117") (pin "2") (pinfunction "2_2") (pintype "unspecified"))
    )
    (net (code "136") (name "Net-(D123-PadA)") (class "Default")
      (node (ref "D123") (pin "A") (pinfunction "A_A") (pintype "unspecified"))
      (node (ref "SW118") (pin "2") (pinfunction "2_2") (pintype "unspecified"))
    )
    (net (code "137") (name "Net-(D125-PadA)") (class "Default")
      (node (ref "D125") (pin "A") (pinfunction "A_A") (pintype "unspecified"))
      (node (ref "SW119") (pin "2") (pinfunction "2_2") (pintype "unspecified"))
    )
    (net (code "138") (name "Net-(D126-PadA)") (class "Default")
      (node (ref "D126") (pin "A") (pinfunction "A_A") (pintype "unspecified"))
      (node (ref "SW120") (pin "2") (pinfunction "2_2") (pintype "unspecified"))
    )
    (net (code "139") (name "Net-(D127-PadA)") (class "Default")
      (node (ref "D127") (pin "A") (pinfunction "A_A") (pintype "unspecified"))
      (node (ref "SW121") (pin "2") (pinfunction "2_2") (pintype "unspecified"))
    )
    (net (code "140") (name "Net-(D128-PadA)") (class "Default")
      (node (ref "D128") (pin "A") (pinfunction "A_A") (pintype "unspecified"))
      (node (ref "SW122") (pin "2") (pinfunction "2_2") (pintype "unspecified"))
    )
    (net (code "141") (name "Net-(D129-PadA)") (class "Default")
      (node (ref "D129") (pin "A") (pinfunction "A_A") (pintype "unspecified"))
      (node (ref "SW123") (pin "2") (pinfunction "2_2") (pintype "unspecified"))
    )
    (net (code "142") (name "Net-(D130-PadA)") (class "Default")
      (node (ref "D130") (pin "A") (pinfunction "A_A") (pintype "unspecified"))
      (node (ref "SW124") (pin "2") (pinfunction "2_2") (pintype "unspecified"))
    )
    (net (code "143") (name "Net-(D131-PadA)") (class "Default")
      (node (ref "D131") (pin "A") (pinfunction "A_A") (pintype "unspecified"))
      (node (ref "SW125") (pin "2") (pinfunction "2_2") (pintype "unspecified"))
    )
    (net (code "144") (name "Net-(D132-PadA)") (class "Default")
      (node (ref "D132") (pin "A") (pinfunction "A_A") (pintype "unspecified"))
      (node (ref "SW126") (pin "2") (pinfunction "2_2") (pintype "unspecified"))
    )
    (net (code "145") (name "Net-(D133-PadA)") (class "Default")
      (node (ref "D133") (pin "A") (pinfunction "A_A") (pintype "unspecified"))
      (node (ref "SW127") (pin "2") (pinfunction "2_2") (pintype "unspecified"))
    )
    (net (code "146") (name "Net-(D134-PadA)") (class "Default")
      (node (ref "D134") (pin "A") (pinfunction "A_A") (pintype "unspecified"))
      (node (ref "SW128") (pin "2") (pinfunction "2_2") (pintype "unspecified"))
    )
    (net (code "147") (name "Net-(D135-PadA)") (class "Default")
      (node (ref "D135") (pin "A") (pinfunction "A_A") (pintype "unspecified"))
      (node (ref "SW129") (pin "2") (pinfunction "2_2") (pintype "unspecified"))
    )
    (net (code "148") (name "Net-(D136-PadA)") (class "Default")
      (node (ref "D136") (pin "A") (pinfunction "A_A") (pintype "unspecified"))
      (node (ref "SW130") (pin "2") (pinfunction "2_2") (pintype "unspecified"))
    )
    (net (code "149") (name "Net-(D137-PadA)") (class "Default")
      (node (ref "D137") (pin "A") (pinfunction "A_A") (pintype "unspecified"))
      (node (ref "SW131") (pin "2") (pinfunction "2_2") (pintype "unspecified"))
    )
    (net (code "150") (name "Net-(D138-PadA)") (class "Default")
      (node (ref "D138") (pin "A") (pinfunction "A_A") (pintype "unspecified"))
      (node (ref "SW132") (pin "2") (pinfunction "2_2") (pintype "unspecified"))
    )
    (net (code "151") (name "Net-(D139-PadA)") (class "Default")
      (node (ref "D139") (pin "A") (pinfunction "A_A") (pintype "unspecified"))
      (node (ref "SW133") (pin "2") (pinfunction "2_2") (pintype "unspecified"))
    )
    (net (code "152") (name "Net-(D140-PadA)") (class "Default")
      (node (ref "D140") (pin "A") (pinfunction "A_A") (pintype "unspecified"))
      (node (ref "SW134") (pin "2") (pinfunction "2_2") (pintype "unspecified"))
    )
    (net (code "153") (name "Net-(LED1-PadC)") (class "Default")
      (node (ref "LED1") (pin "C") (pinfunction "C_C") (pintype "unspecified"))
      (node (ref "R4") (pin "1") (pinfunction "1_1") (pintype "unspecified"))
    )
    (net (code "154") (name "Net-(RESET1-Pad1)") (class "Default")
      (node (ref "RESET1") (pin "1") (pinfunction "1_1") (pintype "unspecified"))
      (node (ref "SJ1") (pin "2") (pinfunction "2_2") (pintype "unspecified"))
    )
    (net (code "155") (name "Net-(U1-PF5(ADC5TMS))") (class "Default")
      (node (ref "R4") (pin "2") (pinfunction "2_2") (pintype "unspecified"))
      (node (ref "U1") (pin "38") (pinfunction "PF5(ADC5TMS)_38") (pintype "unspecified"))
    )
    (net (code "156") (name "Net-(U1-UCAP)") (class "Default")
      (node (ref "C3") (pin "2") (pinfunction "2_2") (pintype "unspecified"))
      (node (ref "U1") (pin "6") (pinfunction "UCAP_6") (pintype "unspecified"))
    )
    (net (code "157") (name "Net-(U1-XTAL1)") (class "Default")
      (node (ref "C1") (pin "2") (pinfunction "2_2") (pintype "unspecified"))
      (node (ref "U1") (pin "17") (pinfunction "XTAL1_17") (pintype "unspecified"))
      (node (ref "Y1") (pin "1") (pinfunction "1_1") (pintype "unspecified"))
    )
    (net (code "158") (name "Net-(U1-XTAL2)") (class "Default")
      (node (ref "C2") (pin "1") (pinfunction "1_1") (pintype "unspecified"))
      (node (ref "U1") (pin "16") (pinfunction "XTAL2_16") (pintype "unspecified"))
      (node (ref "Y1") (pin "3") (pinfunction "2_3") (pintype "unspecified"))
    )
    (net (code "159") (name "Net-(USB1-D+)") (class "Default")
      (node (ref "R2") (pin "1") (pinfunction "1_1") (pintype "unspecified"))
      (node (ref "USB1") (pin "P3") (pinfunction "D+_P3") (pintype "unspecified"))
    )
    (net (code "160") (name "Net-(USB1-D-)") (class "Default")
      (node (ref "R1") (pin "2") (pinfunction "2_2") (pintype "unspecified"))
      (node (ref "USB1") (pin "P2") (pinfunction "D-_P2") (pintype "unspecified"))
    )
    (net (code "161") (name "Reset") (class "Default")
      (node (ref "R3") (pin "1") (pinfunction "1_1") (pintype "unspecified"))
      (node (ref "SJ1") (pin "1") (pinfunction "1_1") (pintype "unspecified"))
      (node (ref "U1") (pin "13") (pinfunction "RESET_13") (pintype "unspecified"))
    )
    (net (code "162") (name "Row 1") (class "Default")
      (node (ref "S1") (pin "C") (pinfunction "LEFT_C") (pintype "unspecified"))
      (node (ref "S2") (pin "C") (pinfunction "LEFT_C") (pintype "unspecified"))
      (node (ref "SW1") (pin "1") (pinfunction "1_1") (pintype "unspecified"))
      (node (ref "SW107") (pin "1") (pinfunction "1_1") (pintype "unspecified"))
      (node (ref "SW11") (pin "1") (pinfunction "1_1") (pintype "unspecified"))
      (node (ref "SW112") (pin "1") (pinfunction "1_1") (pintype "unspecified"))
      (node (ref "SW117") (pin "1") (pinfunction "1_1") (pintype "unspecified"))
      (node (ref "SW121") (pin "1") (pinfunction "1_1") (pintype "unspecified"))
      (node (ref "SW126") (pin "1") (pinfunction "1_1") (pintype "unspecified"))
      (node (ref "SW131") (pin "1") (pinfunction "1_1") (pintype "unspecified"))
      (node (ref "SW16") (pin "1") (pinfunction "1_1") (pintype "unspecified"))
      (node (ref "SW21") (pin "1") (pinfunction "1_1") (pintype "unspecified"))
      (node (ref "SW26") (pin "1") (pinfunction "1_1") (pintype "unspecified"))
      (node (ref "SW31") (pin "1") (pinfunction "1_1") (pintype "unspecified"))
      (node (ref "SW36") (pin "1") (pinfunction "1_1") (pintype "unspecified"))
      (node (ref "SW41") (pin "1") (pinfunction "1_1") (pintype "unspecified"))
      (node (ref "SW46") (pin "1") (pinfunction "1_1") (pintype "unspecified"))
      (node (ref "SW51") (pin "1") (pinfunction "1_1") (pintype "unspecified"))
      (node (ref "SW56") (pin "1") (pinfunction "1_1") (pintype "unspecified"))
      (node (ref "SW6") (pin "1") (pinfunction "1_1") (pintype "unspecified"))
      (node (ref "SW61") (pin "1") (pinfunction "1_1") (pintype "unspecified"))
      (node (ref "SW66") (pin "1") (pinfunction "1_1") (pintype "unspecified"))
      (node (ref "SW73") (pin "1") (pinfunction "1_1") (pintype "unspecified"))
      (node (ref "SW78") (pin "1") (pinfunction "1_1") (pintype "unspecified"))
      (node (ref "SW83") (pin "1") (pinfunction "1_1") (pintype "unspecified"))
      (node (ref "SW88") (pin "1") (pinfunction "1_1") (pintype "unspecified"))
      (node (ref "SW93") (pin "1") (pinfunction "1_1") (pintype "unspecified"))
      (node (ref "SW98") (pin "1") (pinfunction "1_1") (pintype "unspecified"))
      (node (ref "U1") (pin "30") (pinfunction "PB6(OC1BOC4BADC13)_30") (pintype "unspecified"))
    )
    (net (code "163") (name "Row 2") (class "Default")
      (node (ref "S1") (pin "CTR") (pinfunction "CENT_CTR") (pintype "unspecified"))
      (node (ref "S2") (pin "CTR") (pinfunction "CENT_CTR") (pintype "unspecified"))
      (node (ref "SW103") (pin "1") (pinfunction "1_1") (pintype "unspecified"))
      (node (ref "SW108") (pin "1") (pinfunction "1_1") (pintype "unspecified"))
      (node (ref "SW113") (pin "1") (pinfunction "1_1") (pintype "unspecified"))
      (node (ref "SW118") (pin "1") (pinfunction "1_1") (pintype "unspecified"))
      (node (ref "SW12") (pin "1") (pinfunction "1_1") (pintype "unspecified"))
      (node (ref "SW122") (pin "1") (pinfunction "1_1") (pintype "unspecified"))
      (node (ref "SW127") (pin "1") (pinfunction "1_1") (pintype "unspecified"))
      (node (ref "SW132") (pin "1") (pinfunction "1_1") (pintype "unspecified"))
      (node (ref "SW17") (pin "1") (pinfunction "1_1") (pintype "unspecified"))
      (node (ref "SW2") (pin "1") (pinfunction "1_1") (pintype "unspecified"))
      (node (ref "SW22") (pin "1") (pinfunction "1_1") (pintype "unspecified"))
      (node (ref "SW27") (pin "1") (pinfunction "1_1") (pintype "unspecified"))
      (node (ref "SW32") (pin "1") (pinfunction "1_1") (pintype "unspecified"))
      (node (ref "SW37") (pin "1") (pinfunction "1_1") (pintype "unspecified"))
      (node (ref "SW42") (pin "1") (pinfunction "1_1") (pintype "unspecified"))
      (node (ref "SW47") (pin "1") (pinfunction "1_1") (pintype "unspecified"))
      (node (ref "SW52") (pin "1") (pinfunction "1_1") (pintype "unspecified"))
      (node (ref "SW53") (pin "1") (pinfunction "1_1") (pintype "unspecified"))
      (node (ref "SW57") (pin "1") (pinfunction "1_1") (pintype "unspecified"))
      (node (ref "SW62") (pin "1") (pinfunction "1_1") (pintype "unspecified"))
      (node (ref "SW67") (pin "1") (pinfunction "1_1") (pintype "unspecified"))
      (node (ref "SW7") (pin "1") (pinfunction "1_1") (pintype "unspecified"))
      (node (ref "SW74") (pin "1") (pinfunction "1_1") (pintype "unspecified"))
      (node (ref "SW79") (pin "1") (pinfunction "1_1") (pintype "unspecified"))
      (node (ref "SW84") (pin "1") (pinfunction "1_1") (pintype "unspecified"))
      (node (ref "SW89") (pin "1") (pinfunction "1_1") (pintype "unspecified"))
      (node (ref "SW94") (pin "1") (pinfunction "1_1") (pintype "unspecified"))
      (node (ref "SW99") (pin "1") (pinfunction "1_1") (pintype "unspecified"))
      (node (ref "U1") (pin "28") (pinfunction "PB4(ADC11)_28") (pintype "unspecified"))
    )
    (net (code "164") (name "Row 3") (class "Default")
      (node (ref "S1") (pin "A") (pinfunction "UP_A") (pintype "unspecified"))
      (node (ref "S2") (pin "A") (pinfunction "UP_A") (pintype "unspecified"))
      (node (ref "SW100") (pin "1") (pinfunction "1_1") (pintype "unspecified"))
      (node (ref "SW104") (pin "1") (pinfunction "1_1") (pintype "unspecified"))
      (node (ref "SW109") (pin "1") (pinfunction "1_1") (pintype "unspecified"))
      (node (ref "SW114") (pin "1") (pinfunction "1_1") (pintype "unspecified"))
      (node (ref "SW123") (pin "1") (pinfunction "1_1") (pintype "unspecified"))
      (node (ref "SW128") (pin "1") (pinfunction "1_1") (pintype "unspecified"))
      (node (ref "SW13") (pin "1") (pinfunction "1_1") (pintype "unspecified"))
      (node (ref "SW133") (pin "1") (pinfunction "1_1") (pintype "unspecified"))
      (node (ref "SW18") (pin "1") (pinfunction "1_1") (pintype "unspecified"))
      (node (ref "SW23") (pin "1") (pinfunction "1_1") (pintype "unspecified"))
      (node (ref "SW28") (pin "1") (pinfunction "1_1") (pintype "unspecified"))
      (node (ref "SW3") (pin "1") (pinfunction "1_1") (pintype "unspecified"))
      (node (ref "SW33") (pin "1") (pinfunction "1_1") (pintype "unspecified"))
      (node (ref "SW38") (pin "1") (pinfunction "1_1") (pintype "unspecified"))
      (node (ref "SW43") (pin "1") (pinfunction "1_1") (pintype "unspecified"))
      (node (ref "SW48") (pin "1") (pinfunction "1_1") (pintype "unspecified"))
      (node (ref "SW58") (pin "1") (pinfunction "1_1") (pintype "unspecified"))
      (node (ref "SW63") (pin "1") (pinfunction "1_1") (pintype "unspecified"))
      (node (ref "SW68") (pin "1") (pinfunction "1_1") (pintype "unspecified"))
      (node (ref "SW70") (pin "1") (pinfunction "1_1") (pintype "unspecified"))
      (node (ref "SW75") (pin "1") (pinfunction "1_1") (pintype "unspecified"))
      (node (ref "SW8") (pin "1") (pinfunction "1_1") (pintype "unspecified"))
      (node (ref "SW80") (pin "1") (pinfunction "1_1") (pintype "unspecified"))
      (node (ref "SW85") (pin "1") (pinfunction "1_1") (pintype "unspecified"))
      (node (ref "SW90") (pin "1") (pinfunction "1_1") (pintype "unspecified"))
      (node (ref "SW95") (pin "1") (pinfunction "1_1") (pintype "unspecified"))
      (node (ref "U1") (pin "27") (pinfunction "PD7(OC4DADC10T0)_27") (pintype "unspecified"))
    )
    (net (code "165") (name "Row 4") (class "Default")
      (node (ref "S1") (pin "D") (pinfunction "DOWN_D") (pintype "unspecified"))
      (node (ref "S2") (pin "D") (pinfunction "DOWN_D") (pintype "unspecified"))
      (node (ref "SW101") (pin "1") (pinfunction "1_1") (pintype "unspecified"))
      (node (ref "SW105") (pin "1") (pinfunction "1_1") (pintype "unspecified"))
      (node (ref "SW110") (pin "1") (pinfunction "1_1") (pintype "unspecified"))
      (node (ref "SW115") (pin "1") (pinfunction "1_1") (pintype "unspecified"))
      (node (ref "SW119") (pin "1") (pinfunction "1_1") (pintype "unspecified"))
      (node (ref "SW124") (pin "1") (pinfunction "1_1") (pintype "unspecified"))
      (node (ref "SW129") (pin "1") (pinfunction "1_1") (pintype "unspecified"))
      (node (ref "SW134") (pin "1") (pinfunction "1_1") (pintype "unspecified"))
      (node (ref "SW14") (pin "1") (pinfunction "1_1") (pintype "unspecified"))
      (node (ref "SW19") (pin "1") (pinfunction "1_1") (pintype "unspecified"))
      (node (ref "SW24") (pin "1") (pinfunction "1_1") (pintype "unspecified"))
      (node (ref "SW29") (pin "1") (pinfunction "1_1") (pintype "unspecified"))
      (node (ref "SW34") (pin "1") (pinfunction "1_1") (pintype "unspecified"))
      (node (ref "SW39") (pin "1") (pinfunction "1_1") (pintype "unspecified"))
      (node (ref "SW4") (pin "1") (pinfunction "1_1") (pintype "unspecified"))
      (node (ref "SW44") (pin "1") (pinfunction "1_1") (pintype "unspecified"))
      (node (ref "SW49") (pin "1") (pinfunction "1_1") (pintype "unspecified"))
      (node (ref "SW54") (pin "1") (pinfunction "1_1") (pintype "unspecified"))
      (node (ref "SW59") (pin "1") (pinfunction "1_1") (pintype "unspecified"))
      (node (ref "SW64") (pin "1") (pinfunction "1_1") (pintype "unspecified"))
      (node (ref "SW69") (pin "1") (pinfunction "1_1") (pintype "unspecified"))
      (node (ref "SW71") (pin "1") (pinfunction "1_1") (pintype "unspecified"))
      (node (ref "SW76") (pin "1") (pinfunction "1_1") (pintype "unspecified"))
      (node (ref "SW81") (pin "1") (pinfunction "1_1") (pintype "unspecified"))
      (node (ref "SW86") (pin "1") (pinfunction "1_1") (pintype "unspecified"))
      (node (ref "SW9") (pin "1") (pinfunction "1_1") (pintype "unspecified"))
      (node (ref "SW91") (pin "1") (pinfunction "1_1") (pintype "unspecified"))
      (node (ref "SW96") (pin "1") (pinfunction "1_1") (pintype "unspecified"))
      (node (ref "U1") (pin "26") (pinfunction "PD6(T1ADC9!OC4D)_26") (pintype "unspecified"))
    )
    (net (code "166") (name "Row 5") (class "Default")
      (node (ref "S1") (pin "B") (pinfunction "RIGHT_B") (pintype "unspecified"))
      (node (ref "S2") (pin "B") (pinfunction "RIGHT_B") (pintype "unspecified"))
      (node (ref "SW10") (pin "1") (pinfunction "1_1") (pintype "unspecified"))
      (node (ref "SW102") (pin "1") (pinfunction "1_1") (pintype "unspecified"))
      (node (ref "SW106") (pin "1") (pinfunction "1_1") (pintype "unspecified"))
      (node (ref "SW111") (pin "1") (pinfunction "1_1") (pintype "unspecified"))
      (node (ref "SW116") (pin "1") (pinfunction "1_1") (pintype "unspecified"))
      (node (ref "SW120") (pin "1") (pinfunction "1_1") (pintype "unspecified"))
      (node (ref "SW125") (pin "1") (pinfunction "1_1") (pintype "unspecified"))
      (node (ref "SW130") (pin "1") (pinfunction "1_1") (pintype "unspecified"))
      (node (ref "SW15") (pin "1") (pinfunction "1_1") (pintype "unspecified"))
      (node (ref "SW20") (pin "1") (pinfunction "1_1") (pintype "unspecified"))
      (node (ref "SW25") (pin "1") (pinfunction "1_1") (pintype "unspecified"))
      (node (ref "SW30") (pin "1") (pinfunction "1_1") (pintype "unspecified"))
      (node (ref "SW35") (pin "1") (pinfunction "1_1") (pintype "unspecified"))
      (node (ref "SW40") (pin "1") (pinfunction "1_1") (pintype "unspecified"))
      (node (ref "SW45") (pin "1") (pinfunction "1_1") (pintype "unspecified"))
      (node (ref "SW5") (pin "1") (pinfunction "1_1") (pintype "unspecified"))
      (node (ref "SW50") (pin "1") (pinfunction "1_1") (pintype "unspecified"))
      (node (ref "SW55") (pin "1") (pinfunction "1_1") (pintype "unspecified"))
      (node (ref "SW60") (pin "1") (pinfunction "1_1") (pintype "unspecified"))
      (node (ref "SW65") (pin "1") (pinfunction "1_1") (pintype "unspecified"))
      (node (ref "SW72") (pin "1") (pinfunction "1_1") (pintype "unspecified"))
      (node (ref "SW77") (pin "1") (pinfunction "1_1") (pintype "unspecified"))
      (node (ref "SW82") (pin "1") (pinfunction "1_1") (pintype "unspecified"))
      (node (ref "SW87") (pin "1") (pinfunction "1_1") (pintype "unspecified"))
      (node (ref "SW92") (pin "1") (pinfunction "1_1") (pintype "unspecified"))
      (node (ref "SW97") (pin "1") (pinfunction "1_1") (pintype "unspecified"))
      (node (ref "U1") (pin "25") (pinfunction "PD4(ICP1ADC8)_25") (pintype "unspecified"))
    )
    (net (code "167") (name "USB D+") (class "Default")
      (node (ref "R2") (pin "2") (pinfunction "2_2") (pintype "unspecified"))
      (node (ref "U1") (pin "4") (pinfunction "D+_4") (pintype "unspecified"))
    )
    (net (code "168") (name "USB D-") (class "Default")
      (node (ref "R1") (pin "1") (pinfunction "1_1") (pintype "unspecified"))
      (node (ref "U1") (pin "3") (pinfunction "D-_3") (pintype "unspecified"))
    )
    (net (code "169") (name "VCC") (class "Default")
      (node (ref "LED1") (pin "A") (pinfunction "A_A") (pintype "unspecified"))
      (node (ref "R3") (pin "2") (pinfunction "2_2") (pintype "unspecified"))
      (node (ref "U1") (pin "14") (pinfunction "VCC_14") (pintype "unspecified"))
      (node (ref "U1") (pin "2") (pinfunction "UVCC_2") (pintype "unspecified"))
      (node (ref "U1") (pin "24") (pinfunction "AVCC_24") (pintype "unspecified"))
      (node (ref "U1") (pin "34") (pinfunction "VCC1_34") (pintype "unspecified"))
      (node (ref "U1") (pin "44") (pinfunction "AVCC1_44") (pintype "unspecified"))
      (node (ref "U1") (pin "7") (pinfunction "VBUS_7") (pintype "unspecified"))
      (node (ref "USB1") (pin "P1") (pinfunction "VUSB_P1") (pintype "unspecified"))
    )
    (net (code "170") (name "unconnected-(D36-PadA)") (class "Default")
      (node (ref "D36") (pin "A") (pinfunction "A_A") (pintype "unspecified"))
    )
    (net (code "171") (name "unconnected-(D53-PadA)") (class "Default")
      (node (ref "D53") (pin "A") (pinfunction "A_A") (pintype "unspecified"))
    )
    (net (code "172") (name "unconnected-(D107-PadA)") (class "Default")
      (node (ref "D107") (pin "A") (pinfunction "A_A") (pintype "unspecified"))
    )
    (net (code "173") (name "unconnected-(D124-PadA)") (class "Default")
      (node (ref "D124") (pin "A") (pinfunction "A_A") (pintype "unspecified"))
    )
    (net (code "174") (name "unconnected-(U1-AREF-Pad42)") (class "Default")
      (node (ref "U1") (pin "42") (pinfunction "AREF_42") (pintype "unspecified"))
    )
    (net (code "175") (name "unconnected-(U1-PE6(INT.6AIN0)-Pad1)") (class "Default")
      (node (ref "U1") (pin "1") (pinfunction "PE6(INT.6AIN0)_1") (pintype "unspecified"))
    )
    (net (code "176") (name "unconnected-(U1-PF0(ADC0)-Pad41)") (class "Default")
      (node (ref "U1") (pin "41") (pinfunction "PF0(ADC0)_41") (pintype "unspecified"))
    )
    (net (code "177") (name "unconnected-(U1-PF1(ADC1)-Pad40)") (class "Default")
      (node (ref "U1") (pin "40") (pinfunction "PF1(ADC1)_40") (pintype "unspecified"))
    )
    (net (code "178") (name "unconnected-(U1-PF4(ADC4TCK)-Pad39)") (class "Default")
      (node (ref "U1") (pin "39") (pinfunction "PF4(ADC4TCK)_39") (pintype "unspecified"))
    )
    (net (code "179") (name "unconnected-(USB1-BODY-PadBODY@1)") (class "Default")
      (node (ref "USB1") (pin "BODY@1") (pinfunction "BODY_BODY@1") (pintype "unspecified"))
    )
    (net (code "180") (name "unconnected-(USB1-BODY-PadBODY@2)") (class "Default")
      (node (ref "USB1") (pin "BODY@2") (pinfunction "BODY_BODY@2") (pintype "unspecified"))
    )
    (net (code "181") (name "unconnected-(USB1-BODY-PadBODY@3)") (class "Default")
      (node (ref "USB1") (pin "BODY@3") (pinfunction "BODY_BODY@3") (pintype "unspecified"))
    )
    (net (code "182") (name "unconnected-(USB1-BODY-PadBODY@4)") (class "Default")
      (node (ref "USB1") (pin "BODY@4") (pinfunction "BODY_BODY@4") (pintype "unspecified"))
    )
    (net (code "183") (name "unconnected-(USB1-USBID-PadP4)") (class "Default")
      (node (ref "USB1") (pin "P4") (pinfunction "USBID_P4") (pintype "unspecified"))
    )
  )
)
